# main.net
KiCad netlist of a schematic drawn in EAGLE
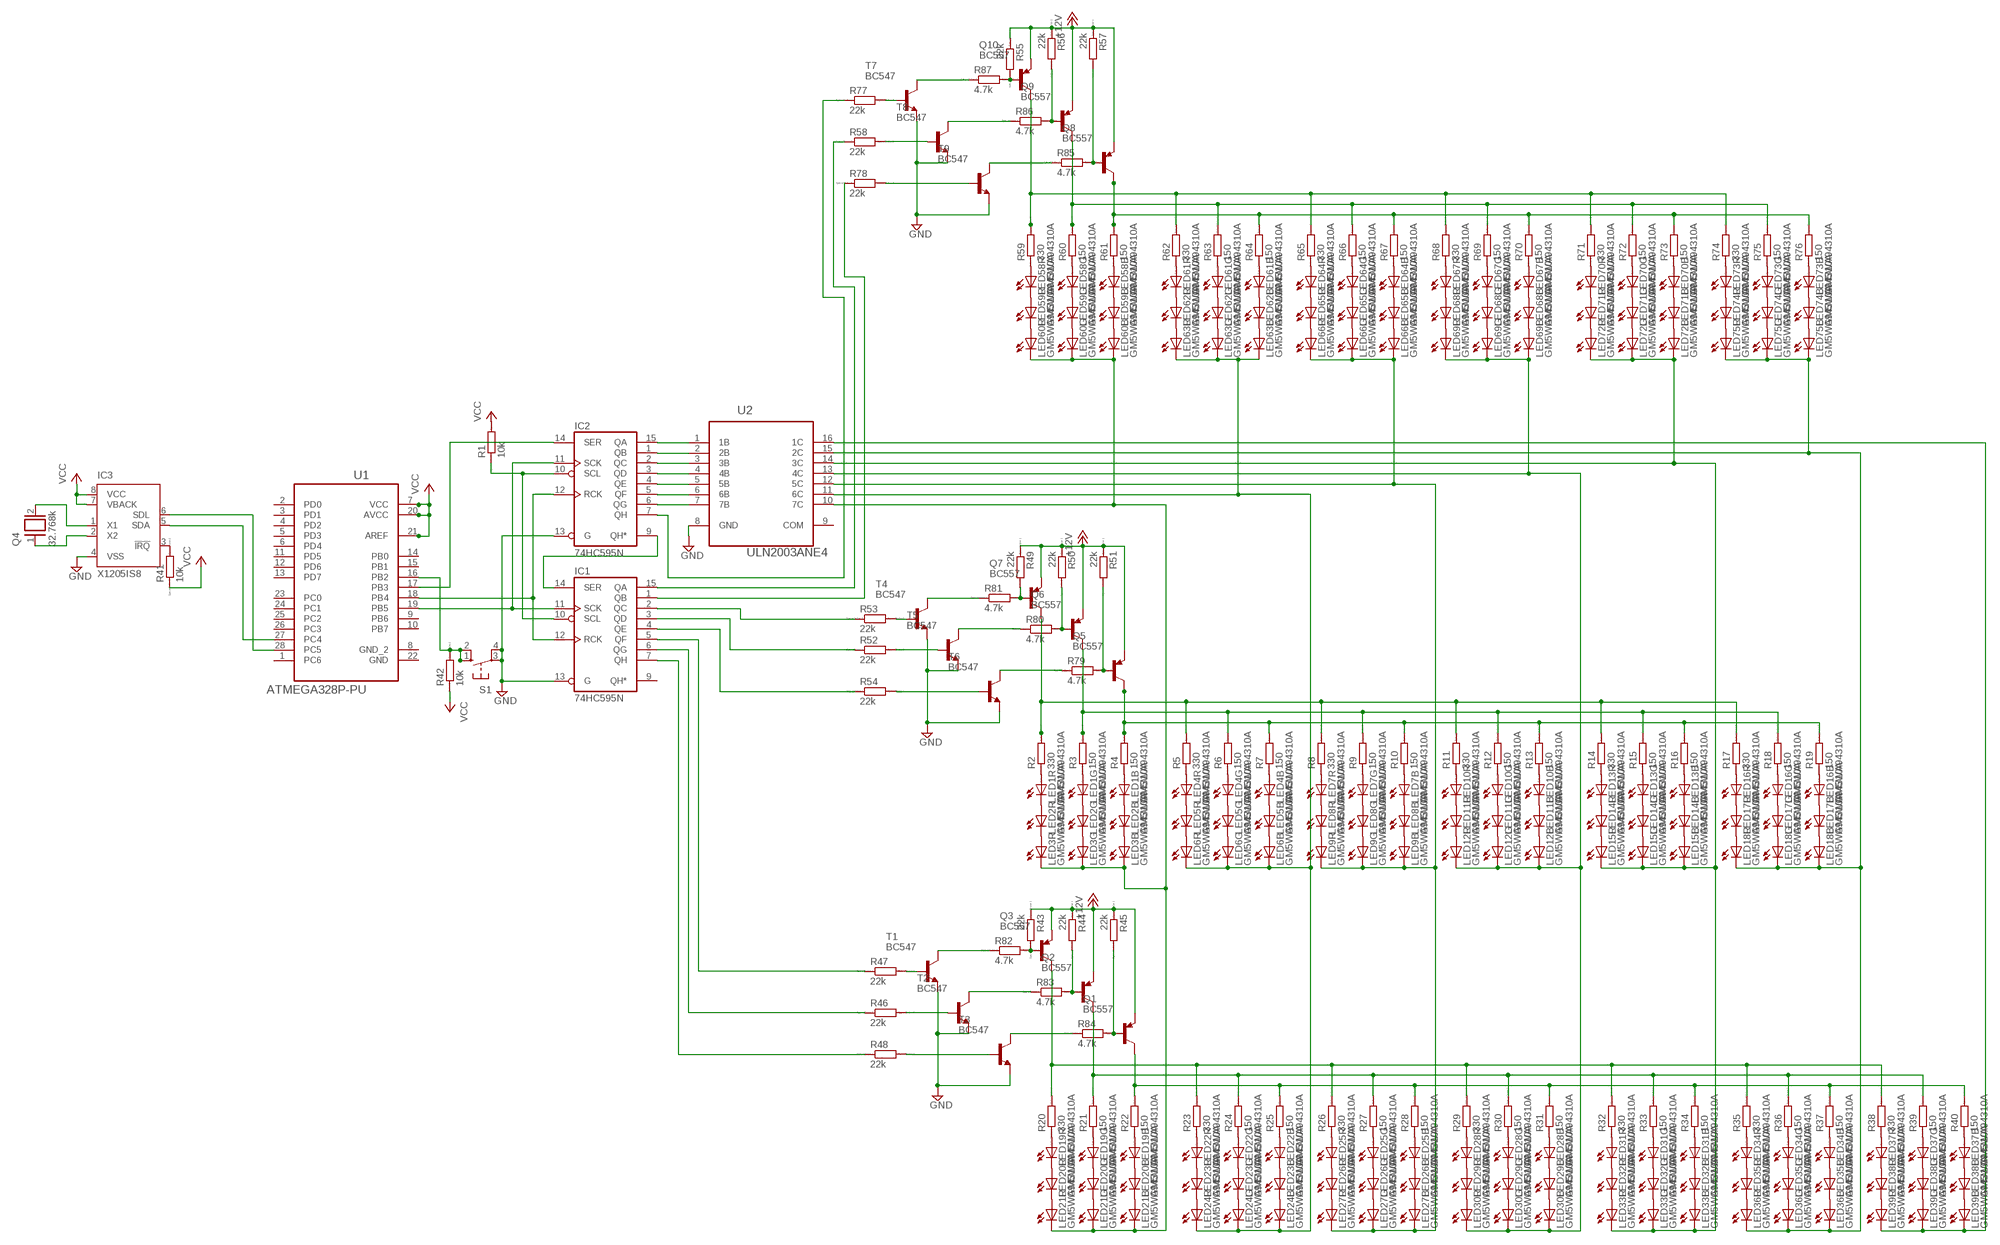
[diagram p0: schematic, sheet 1]

(export (version "E")
  (design (tool "Eeschema 10.0.6"))
  (components
    (comp (ref "IC1")
      (value "74HC595N")
      (footprint "eagle-import:DIL16")
      (libsource (lib "eagle-import") (part "74595NHC"))
    )
    (comp (ref "IC2")
      (value "74HC595N")
      (footprint "eagle-import:DIL16")
      (libsource (lib "eagle-import") (part "74595NHC"))
    )
    (comp (ref "IC3")
      (value "X1205IS8")
      (footprint "eagle-import:SO-08")
      (libsource (lib "eagle-import") (part "X1205S8I"))
    )
    (comp (ref "LED1")
      (value "GM5WA94310A")
      (footprint "eagle-import:GM5WA94310A")
      (libsource (lib "eagle-import") (part "GM5WA94310A"))
    )
    (comp (ref "LED2")
      (value "GM5WA94310A")
      (footprint "eagle-import:GM5WA94310A")
      (libsource (lib "eagle-import") (part "GM5WA94310A"))
    )
    (comp (ref "LED3")
      (value "GM5WA94310A")
      (footprint "eagle-import:GM5WA94310A")
      (libsource (lib "eagle-import") (part "GM5WA94310A"))
    )
    (comp (ref "LED4")
      (value "GM5WA94310A")
      (footprint "eagle-import:GM5WA94310A")
      (libsource (lib "eagle-import") (part "GM5WA94310A"))
    )
    (comp (ref "LED5")
      (value "GM5WA94310A")
      (footprint "eagle-import:GM5WA94310A")
      (libsource (lib "eagle-import") (part "GM5WA94310A"))
    )
    (comp (ref "LED6")
      (value "GM5WA94310A")
      (footprint "eagle-import:GM5WA94310A")
      (libsource (lib "eagle-import") (part "GM5WA94310A"))
    )
    (comp (ref "LED7")
      (value "GM5WA94310A")
      (footprint "eagle-import:GM5WA94310A")
      (libsource (lib "eagle-import") (part "GM5WA94310A"))
    )
    (comp (ref "LED8")
      (value "GM5WA94310A")
      (footprint "eagle-import:GM5WA94310A")
      (libsource (lib "eagle-import") (part "GM5WA94310A"))
    )
    (comp (ref "LED9")
      (value "GM5WA94310A")
      (footprint "eagle-import:GM5WA94310A")
      (libsource (lib "eagle-import") (part "GM5WA94310A"))
    )
    (comp (ref "LED10")
      (value "GM5WA94310A")
      (footprint "eagle-import:GM5WA94310A")
      (libsource (lib "eagle-import") (part "GM5WA94310A"))
    )
    (comp (ref "LED11")
      (value "GM5WA94310A")
      (footprint "eagle-import:GM5WA94310A")
      (libsource (lib "eagle-import") (part "GM5WA94310A"))
    )
    (comp (ref "LED12")
      (value "GM5WA94310A")
      (footprint "eagle-import:GM5WA94310A")
      (libsource (lib "eagle-import") (part "GM5WA94310A"))
    )
    (comp (ref "LED13")
      (value "GM5WA94310A")
      (footprint "eagle-import:GM5WA94310A")
      (libsource (lib "eagle-import") (part "GM5WA94310A"))
    )
    (comp (ref "LED14")
      (value "GM5WA94310A")
      (footprint "eagle-import:GM5WA94310A")
      (libsource (lib "eagle-import") (part "GM5WA94310A"))
    )
    (comp (ref "LED15")
      (value "GM5WA94310A")
      (footprint "eagle-import:GM5WA94310A")
      (libsource (lib "eagle-import") (part "GM5WA94310A"))
    )
    (comp (ref "LED16")
      (value "GM5WA94310A")
      (footprint "eagle-import:GM5WA94310A")
      (libsource (lib "eagle-import") (part "GM5WA94310A"))
    )
    (comp (ref "LED17")
      (value "GM5WA94310A")
      (footprint "eagle-import:GM5WA94310A")
      (libsource (lib "eagle-import") (part "GM5WA94310A"))
    )
    (comp (ref "LED18")
      (value "GM5WA94310A")
      (footprint "eagle-import:GM5WA94310A")
      (libsource (lib "eagle-import") (part "GM5WA94310A"))
    )
    (comp (ref "LED19")
      (value "GM5WA94310A")
      (footprint "eagle-import:GM5WA94310A")
      (libsource (lib "eagle-import") (part "GM5WA94310A"))
    )
    (comp (ref "LED20")
      (value "GM5WA94310A")
      (footprint "eagle-import:GM5WA94310A")
      (libsource (lib "eagle-import") (part "GM5WA94310A"))
    )
    (comp (ref "LED21")
      (value "GM5WA94310A")
      (footprint "eagle-import:GM5WA94310A")
      (libsource (lib "eagle-import") (part "GM5WA94310A"))
    )
    (comp (ref "LED22")
      (value "GM5WA94310A")
      (footprint "eagle-import:GM5WA94310A")
      (libsource (lib "eagle-import") (part "GM5WA94310A"))
    )
    (comp (ref "LED23")
      (value "GM5WA94310A")
      (footprint "eagle-import:GM5WA94310A")
      (libsource (lib "eagle-import") (part "GM5WA94310A"))
    )
    (comp (ref "LED24")
      (value "GM5WA94310A")
      (footprint "eagle-import:GM5WA94310A")
      (libsource (lib "eagle-import") (part "GM5WA94310A"))
    )
    (comp (ref "LED25")
      (value "GM5WA94310A")
      (footprint "eagle-import:GM5WA94310A")
      (libsource (lib "eagle-import") (part "GM5WA94310A"))
    )
    (comp (ref "LED26")
      (value "GM5WA94310A")
      (footprint "eagle-import:GM5WA94310A")
      (libsource (lib "eagle-import") (part "GM5WA94310A"))
    )
    (comp (ref "LED27")
      (value "GM5WA94310A")
      (footprint "eagle-import:GM5WA94310A")
      (libsource (lib "eagle-import") (part "GM5WA94310A"))
    )
    (comp (ref "LED28")
      (value "GM5WA94310A")
      (footprint "eagle-import:GM5WA94310A")
      (libsource (lib "eagle-import") (part "GM5WA94310A"))
    )
    (comp (ref "LED29")
      (value "GM5WA94310A")
      (footprint "eagle-import:GM5WA94310A")
      (libsource (lib "eagle-import") (part "GM5WA94310A"))
    )
    (comp (ref "LED30")
      (value "GM5WA94310A")
      (footprint "eagle-import:GM5WA94310A")
      (libsource (lib "eagle-import") (part "GM5WA94310A"))
    )
    (comp (ref "LED31")
      (value "GM5WA94310A")
      (footprint "eagle-import:GM5WA94310A")
      (libsource (lib "eagle-import") (part "GM5WA94310A"))
    )
    (comp (ref "LED32")
      (value "GM5WA94310A")
      (footprint "eagle-import:GM5WA94310A")
      (libsource (lib "eagle-import") (part "GM5WA94310A"))
    )
    (comp (ref "LED33")
      (value "GM5WA94310A")
      (footprint "eagle-import:GM5WA94310A")
      (libsource (lib "eagle-import") (part "GM5WA94310A"))
    )
    (comp (ref "LED34")
      (value "GM5WA94310A")
      (footprint "eagle-import:GM5WA94310A")
      (libsource (lib "eagle-import") (part "GM5WA94310A"))
    )
    (comp (ref "LED35")
      (value "GM5WA94310A")
      (footprint "eagle-import:GM5WA94310A")
      (libsource (lib "eagle-import") (part "GM5WA94310A"))
    )
    (comp (ref "LED36")
      (value "GM5WA94310A")
      (footprint "eagle-import:GM5WA94310A")
      (libsource (lib "eagle-import") (part "GM5WA94310A"))
    )
    (comp (ref "LED37")
      (value "GM5WA94310A")
      (footprint "eagle-import:GM5WA94310A")
      (libsource (lib "eagle-import") (part "GM5WA94310A"))
    )
    (comp (ref "LED38")
      (value "GM5WA94310A")
      (footprint "eagle-import:GM5WA94310A")
      (libsource (lib "eagle-import") (part "GM5WA94310A"))
    )
    (comp (ref "LED39")
      (value "GM5WA94310A")
      (footprint "eagle-import:GM5WA94310A")
      (libsource (lib "eagle-import") (part "GM5WA94310A"))
    )
    (comp (ref "LED58")
      (value "GM5WA94310A")
      (footprint "eagle-import:GM5WA94310A")
      (libsource (lib "eagle-import") (part "GM5WA94310A"))
    )
    (comp (ref "LED59")
      (value "GM5WA94310A")
      (footprint "eagle-import:GM5WA94310A")
      (libsource (lib "eagle-import") (part "GM5WA94310A"))
    )
    (comp (ref "LED60")
      (value "GM5WA94310A")
      (footprint "eagle-import:GM5WA94310A")
      (libsource (lib "eagle-import") (part "GM5WA94310A"))
    )
    (comp (ref "LED61")
      (value "GM5WA94310A")
      (footprint "eagle-import:GM5WA94310A")
      (libsource (lib "eagle-import") (part "GM5WA94310A"))
    )
    (comp (ref "LED62")
      (value "GM5WA94310A")
      (footprint "eagle-import:GM5WA94310A")
      (libsource (lib "eagle-import") (part "GM5WA94310A"))
    )
    (comp (ref "LED63")
      (value "GM5WA94310A")
      (footprint "eagle-import:GM5WA94310A")
      (libsource (lib "eagle-import") (part "GM5WA94310A"))
    )
    (comp (ref "LED64")
      (value "GM5WA94310A")
      (footprint "eagle-import:GM5WA94310A")
      (libsource (lib "eagle-import") (part "GM5WA94310A"))
    )
    (comp (ref "LED65")
      (value "GM5WA94310A")
      (footprint "eagle-import:GM5WA94310A")
      (libsource (lib "eagle-import") (part "GM5WA94310A"))
    )
    (comp (ref "LED66")
      (value "GM5WA94310A")
      (footprint "eagle-import:GM5WA94310A")
      (libsource (lib "eagle-import") (part "GM5WA94310A"))
    )
    (comp (ref "LED67")
      (value "GM5WA94310A")
      (footprint "eagle-import:GM5WA94310A")
      (libsource (lib "eagle-import") (part "GM5WA94310A"))
    )
    (comp (ref "LED68")
      (value "GM5WA94310A")
      (footprint "eagle-import:GM5WA94310A")
      (libsource (lib "eagle-import") (part "GM5WA94310A"))
    )
    (comp (ref "LED69")
      (value "GM5WA94310A")
      (footprint "eagle-import:GM5WA94310A")
      (libsource (lib "eagle-import") (part "GM5WA94310A"))
    )
    (comp (ref "LED70")
      (value "GM5WA94310A")
      (footprint "eagle-import:GM5WA94310A")
      (libsource (lib "eagle-import") (part "GM5WA94310A"))
    )
    (comp (ref "LED71")
      (value "GM5WA94310A")
      (footprint "eagle-import:GM5WA94310A")
      (libsource (lib "eagle-import") (part "GM5WA94310A"))
    )
    (comp (ref "LED72")
      (value "GM5WA94310A")
      (footprint "eagle-import:GM5WA94310A")
      (libsource (lib "eagle-import") (part "GM5WA94310A"))
    )
    (comp (ref "LED73")
      (value "GM5WA94310A")
      (footprint "eagle-import:GM5WA94310A")
      (libsource (lib "eagle-import") (part "GM5WA94310A"))
    )
    (comp (ref "LED74")
      (value "GM5WA94310A")
      (footprint "eagle-import:GM5WA94310A")
      (libsource (lib "eagle-import") (part "GM5WA94310A"))
    )
    (comp (ref "LED75")
      (value "GM5WA94310A")
      (footprint "eagle-import:GM5WA94310A")
      (libsource (lib "eagle-import") (part "GM5WA94310A"))
    )
    (comp (ref "Q1")
      (value "BC557")
      (footprint "eagle-import:TO92-EBC")
      (libsource (lib "eagle-import") (part "BC557"))
    )
    (comp (ref "Q2")
      (value "BC557")
      (footprint "eagle-import:TO92-EBC")
      (libsource (lib "eagle-import") (part "BC557"))
    )
    (comp (ref "Q3")
      (value "BC557")
      (footprint "eagle-import:TO92-EBC")
      (libsource (lib "eagle-import") (part "BC557"))
    )
    (comp (ref "Q4")
      (value "32.768k")
      (footprint "eagle-import:QS")
      (libsource (lib "eagle-import") (part "XTAL/S"))
    )
    (comp (ref "Q5")
      (value "BC557")
      (footprint "eagle-import:TO92-EBC")
      (libsource (lib "eagle-import") (part "BC557"))
    )
    (comp (ref "Q6")
      (value "BC557")
      (footprint "eagle-import:TO92-EBC")
      (libsource (lib "eagle-import") (part "BC557"))
    )
    (comp (ref "Q7")
      (value "BC557")
      (footprint "eagle-import:TO92-EBC")
      (libsource (lib "eagle-import") (part "BC557"))
    )
    (comp (ref "Q8")
      (value "BC557")
      (footprint "eagle-import:TO92-EBC")
      (libsource (lib "eagle-import") (part "BC557"))
    )
    (comp (ref "Q9")
      (value "BC557")
      (footprint "eagle-import:TO92-EBC")
      (libsource (lib "eagle-import") (part "BC557"))
    )
    (comp (ref "Q10")
      (value "BC557")
      (footprint "eagle-import:TO92-EBC")
      (libsource (lib "eagle-import") (part "BC557"))
    )
    (comp (ref "R1")
      (value "10k")
      (footprint "eagle-import:0204_7")
      (libsource (lib "eagle-import") (part "R0204/7"))
    )
    (comp (ref "R2")
      (value "330")
      (footprint "eagle-import:0204_7")
      (libsource (lib "eagle-import") (part "R0204/7"))
    )
    (comp (ref "R3")
      (value "150")
      (footprint "eagle-import:0204_7")
      (libsource (lib "eagle-import") (part "R0204/7"))
    )
    (comp (ref "R4")
      (value "150")
      (footprint "eagle-import:0204_7")
      (libsource (lib "eagle-import") (part "R0204/7"))
    )
    (comp (ref "R5")
      (value "330")
      (footprint "eagle-import:0204_7")
      (libsource (lib "eagle-import") (part "R0204/7"))
    )
    (comp (ref "R6")
      (value "150")
      (footprint "eagle-import:0204_7")
      (libsource (lib "eagle-import") (part "R0204/7"))
    )
    (comp (ref "R7")
      (value "150")
      (footprint "eagle-import:0204_7")
      (libsource (lib "eagle-import") (part "R0204/7"))
    )
    (comp (ref "R8")
      (value "330")
      (footprint "eagle-import:0204_7")
      (libsource (lib "eagle-import") (part "R0204/7"))
    )
    (comp (ref "R9")
      (value "150")
      (footprint "eagle-import:0204_7")
      (libsource (lib "eagle-import") (part "R0204/7"))
    )
    (comp (ref "R10")
      (value "150")
      (footprint "eagle-import:0204_7")
      (libsource (lib "eagle-import") (part "R0204/7"))
    )
    (comp (ref "R11")
      (value "330")
      (footprint "eagle-import:0204_7")
      (libsource (lib "eagle-import") (part "R0204/7"))
    )
    (comp (ref "R12")
      (value "150")
      (footprint "eagle-import:0204_7")
      (libsource (lib "eagle-import") (part "R0204/7"))
    )
    (comp (ref "R13")
      (value "150")
      (footprint "eagle-import:0204_7")
      (libsource (lib "eagle-import") (part "R0204/7"))
    )
    (comp (ref "R14")
      (value "330")
      (footprint "eagle-import:0204_7")
      (libsource (lib "eagle-import") (part "R0204/7"))
    )
    (comp (ref "R15")
      (value "150")
      (footprint "eagle-import:0204_7")
      (libsource (lib "eagle-import") (part "R0204/7"))
    )
    (comp (ref "R16")
      (value "150")
      (footprint "eagle-import:0204_7")
      (libsource (lib "eagle-import") (part "R0204/7"))
    )
    (comp (ref "R17")
      (value "330")
      (footprint "eagle-import:0204_7")
      (libsource (lib "eagle-import") (part "R0204/7"))
    )
    (comp (ref "R18")
      (value "150")
      (footprint "eagle-import:0204_7")
      (libsource (lib "eagle-import") (part "R0204/7"))
    )
    (comp (ref "R19")
      (value "150")
      (footprint "eagle-import:0204_7")
      (libsource (lib "eagle-import") (part "R0204/7"))
    )
    (comp (ref "R20")
      (value "330")
      (footprint "eagle-import:0204_7")
      (libsource (lib "eagle-import") (part "R0204/7"))
    )
    (comp (ref "R21")
      (value "150")
      (footprint "eagle-import:0204_7")
      (libsource (lib "eagle-import") (part "R0204/7"))
    )
    (comp (ref "R22")
      (value "150")
      (footprint "eagle-import:0204_7")
      (libsource (lib "eagle-import") (part "R0204/7"))
    )
    (comp (ref "R23")
      (value "330")
      (footprint "eagle-import:0204_7")
      (libsource (lib "eagle-import") (part "R0204/7"))
    )
    (comp (ref "R24")
      (value "150")
      (footprint "eagle-import:0204_7")
      (libsource (lib "eagle-import") (part "R0204/7"))
    )
    (comp (ref "R25")
      (value "150")
      (footprint "eagle-import:0204_7")
      (libsource (lib "eagle-import") (part "R0204/7"))
    )
    (comp (ref "R26")
      (value "330")
      (footprint "eagle-import:0204_7")
      (libsource (lib "eagle-import") (part "R0204/7"))
    )
    (comp (ref "R27")
      (value "150")
      (footprint "eagle-import:0204_7")
      (libsource (lib "eagle-import") (part "R0204/7"))
    )
    (comp (ref "R28")
      (value "150")
      (footprint "eagle-import:0204_7")
      (libsource (lib "eagle-import") (part "R0204/7"))
    )
    (comp (ref "R29")
      (value "330")
      (footprint "eagle-import:0204_7")
      (libsource (lib "eagle-import") (part "R0204/7"))
    )
    (comp (ref "R30")
      (value "150")
      (footprint "eagle-import:0204_7")
      (libsource (lib "eagle-import") (part "R0204/7"))
    )
    (comp (ref "R31")
      (value "150")
      (footprint "eagle-import:0204_7")
      (libsource (lib "eagle-import") (part "R0204/7"))
    )
    (comp (ref "R32")
      (value "330")
      (footprint "eagle-import:0204_7")
      (libsource (lib "eagle-import") (part "R0204/7"))
    )
    (comp (ref "R33")
      (value "150")
      (footprint "eagle-import:0204_7")
      (libsource (lib "eagle-import") (part "R0204/7"))
    )
    (comp (ref "R34")
      (value "150")
      (footprint "eagle-import:0204_7")
      (libsource (lib "eagle-import") (part "R0204/7"))
    )
    (comp (ref "R35")
      (value "330")
      (footprint "eagle-import:0204_7")
      (libsource (lib "eagle-import") (part "R0204/7"))
    )
    (comp (ref "R36")
      (value "150")
      (footprint "eagle-import:0204_7")
      (libsource (lib "eagle-import") (part "R0204/7"))
    )
    (comp (ref "R37")
      (value "150")
      (footprint "eagle-import:0204_7")
      (libsource (lib "eagle-import") (part "R0204/7"))
    )
    (comp (ref "R38")
      (value "330")
      (footprint "eagle-import:0204_7")
      (libsource (lib "eagle-import") (part "R0204/7"))
    )
    (comp (ref "R39")
      (value "150")
      (footprint "eagle-import:0204_7")
      (libsource (lib "eagle-import") (part "R0204/7"))
    )
    (comp (ref "R40")
      (value "150")
      (footprint "eagle-import:0204_7")
      (libsource (lib "eagle-import") (part "R0204/7"))
    )
    (comp (ref "R41")
      (value "10k")
      (footprint "eagle-import:0204_7")
      (libsource (lib "eagle-import") (part "R0204/7"))
    )
    (comp (ref "R42")
      (value "10k")
      (footprint "eagle-import:0204_7")
      (libsource (lib "eagle-import") (part "R0204/7"))
    )
    (comp (ref "R43")
      (value "22k")
      (footprint "eagle-import:0204_7")
      (libsource (lib "eagle-import") (part "R0204/7"))
    )
    (comp (ref "R44")
      (value "22k")
      (footprint "eagle-import:0204_7")
      (libsource (lib "eagle-import") (part "R0204/7"))
    )
    (comp (ref "R45")
      (value "22k")
      (footprint "eagle-import:0204_7")
      (libsource (lib "eagle-import") (part "R0204/7"))
    )
    (comp (ref "R46")
      (value "22k")
      (footprint "eagle-import:0204_7")
      (libsource (lib "eagle-import") (part "R0204/7"))
    )
    (comp (ref "R47")
      (value "22k")
      (footprint "eagle-import:0204_7")
      (libsource (lib "eagle-import") (part "R0204/7"))
    )
    (comp (ref "R48")
      (value "22k")
      (footprint "eagle-import:0204_7")
      (libsource (lib "eagle-import") (part "R0204/7"))
    )
    (comp (ref "R49")
      (value "22k")
      (footprint "eagle-import:0204_7")
      (libsource (lib "eagle-import") (part "R0204/7"))
    )
    (comp (ref "R50")
      (value "22k")
      (footprint "eagle-import:0204_7")
      (libsource (lib "eagle-import") (part "R0204/7"))
    )
    (comp (ref "R51")
      (value "22k")
      (footprint "eagle-import:0204_7")
      (libsource (lib "eagle-import") (part "R0204/7"))
    )
    (comp (ref "R52")
      (value "22k")
      (footprint "eagle-import:0204_7")
      (libsource (lib "eagle-import") (part "R0204/7"))
    )
    (comp (ref "R53")
      (value "22k")
      (footprint "eagle-import:0204_7")
      (libsource (lib "eagle-import") (part "R0204/7"))
    )
    (comp (ref "R54")
      (value "22k")
      (footprint "eagle-import:0204_7")
      (libsource (lib "eagle-import") (part "R0204/7"))
    )
    (comp (ref "R55")
      (value "22k")
      (footprint "eagle-import:0204_7")
      (libsource (lib "eagle-import") (part "R0204/7"))
    )
    (comp (ref "R56")
      (value "22k")
      (footprint "eagle-import:0204_7")
      (libsource (lib "eagle-import") (part "R0204/7"))
    )
    (comp (ref "R57")
      (value "22k")
      (footprint "eagle-import:0204_7")
      (libsource (lib "eagle-import") (part "R0204/7"))
    )
    (comp (ref "R58")
      (value "22k")
      (footprint "eagle-import:0204_7")
      (libsource (lib "eagle-import") (part "R0204/7"))
    )
    (comp (ref "R59")
      (value "330")
      (footprint "eagle-import:0204_7")
      (libsource (lib "eagle-import") (part "R0204/7"))
    )
    (comp (ref "R60")
      (value "150")
      (footprint "eagle-import:0204_7")
      (libsource (lib "eagle-import") (part "R0204/7"))
    )
    (comp (ref "R61")
      (value "150")
      (footprint "eagle-import:0204_7")
      (libsource (lib "eagle-import") (part "R0204/7"))
    )
    (comp (ref "R62")
      (value "330")
      (footprint "eagle-import:0204_7")
      (libsource (lib "eagle-import") (part "R0204/7"))
    )
    (comp (ref "R63")
      (value "150")
      (footprint "eagle-import:0204_7")
      (libsource (lib "eagle-import") (part "R0204/7"))
    )
    (comp (ref "R64")
      (value "150")
      (footprint "eagle-import:0204_7")
      (libsource (lib "eagle-import") (part "R0204/7"))
    )
    (comp (ref "R65")
      (value "330")
      (footprint "eagle-import:0204_7")
      (libsource (lib "eagle-import") (part "R0204/7"))
    )
    (comp (ref "R66")
      (value "150")
      (footprint "eagle-import:0204_7")
      (libsource (lib "eagle-import") (part "R0204/7"))
    )
    (comp (ref "R67")
      (value "150")
      (footprint "eagle-import:0204_7")
      (libsource (lib "eagle-import") (part "R0204/7"))
    )
    (comp (ref "R68")
      (value "330")
      (footprint "eagle-import:0204_7")
      (libsource (lib "eagle-import") (part "R0204/7"))
    )
    (comp (ref "R69")
      (value "150")
      (footprint "eagle-import:0204_7")
      (libsource (lib "eagle-import") (part "R0204/7"))
    )
    (comp (ref "R70")
      (value "150")
      (footprint "eagle-import:0204_7")
      (libsource (lib "eagle-import") (part "R0204/7"))
    )
    (comp (ref "R71")
      (value "330")
      (footprint "eagle-import:0204_7")
      (libsource (lib "eagle-import") (part "R0204/7"))
    )
    (comp (ref "R72")
      (value "150")
      (footprint "eagle-import:0204_7")
      (libsource (lib "eagle-import") (part "R0204/7"))
    )
    (comp (ref "R73")
      (value "150")
      (footprint "eagle-import:0204_7")
      (libsource (lib "eagle-import") (part "R0204/7"))
    )
    (comp (ref "R74")
      (value "330")
      (footprint "eagle-import:0204_7")
      (libsource (lib "eagle-import") (part "R0204/7"))
    )
    (comp (ref "R75")
      (value "150")
      (footprint "eagle-import:0204_7")
      (libsource (lib "eagle-import") (part "R0204/7"))
    )
    (comp (ref "R76")
      (value "150")
      (footprint "eagle-import:0204_7")
      (libsource (lib "eagle-import") (part "R0204/7"))
    )
    (comp (ref "R77")
      (value "22k")
      (footprint "eagle-import:0204_7")
      (libsource (lib "eagle-import") (part "R0204/7"))
    )
    (comp (ref "R78")
      (value "22k")
      (footprint "eagle-import:0204_7")
      (libsource (lib "eagle-import") (part "R0204/7"))
    )
    (comp (ref "R79")
      (value "4.7k")
      (footprint "eagle-import:0204_7")
      (libsource (lib "eagle-import") (part "R0204/7"))
    )
    (comp (ref "R80")
      (value "4.7k")
      (footprint "eagle-import:0204_7")
      (libsource (lib "eagle-import") (part "R0204/7"))
    )
    (comp (ref "R81")
      (value "4.7k")
      (footprint "eagle-import:0204_7")
      (libsource (lib "eagle-import") (part "R0204/7"))
    )
    (comp (ref "R82")
      (value "4.7k")
      (footprint "eagle-import:0204_7")
      (libsource (lib "eagle-import") (part "R0204/7"))
    )
    (comp (ref "R83")
      (value "4.7k")
      (footprint "eagle-import:0204_7")
      (libsource (lib "eagle-import") (part "R0204/7"))
    )
    (comp (ref "R84")
      (value "4.7k")
      (footprint "eagle-import:0204_7")
      (libsource (lib "eagle-import") (part "R0204/7"))
    )
    (comp (ref "R85")
      (value "4.7k")
      (footprint "eagle-import:0204_7")
      (libsource (lib "eagle-import") (part "R0204/7"))
    )
    (comp (ref "R86")
      (value "4.7k")
      (footprint "eagle-import:0204_7")
      (libsource (lib "eagle-import") (part "R0204/7"))
    )
    (comp (ref "R87")
      (value "4.7k")
      (footprint "eagle-import:0204_7")
      (libsource (lib "eagle-import") (part "R0204/7"))
    )
    (comp (ref "S1")
      (value "10-XX")
      (footprint "eagle-import:B3F-10XX")
      (fields (field (name "MPN") "B3F-1000"))
      (libsource (lib "eagle-import") (part "10-XX"))
    )
    (comp (ref "T1")
      (value "BC547")
      (footprint "eagle-import:TO92")
      (libsource (lib "eagle-import") (part "BC547"))
    )
    (comp (ref "T2")
      (value "BC547")
      (footprint "eagle-import:TO92")
      (libsource (lib "eagle-import") (part "BC547"))
    )
    (comp (ref "T3")
      (value "BC547")
      (footprint "eagle-import:TO92")
      (libsource (lib "eagle-import") (part "BC547"))
    )
    (comp (ref "T4")
      (value "BC547")
      (footprint "eagle-import:TO92")
      (libsource (lib "eagle-import") (part "BC547"))
    )
    (comp (ref "T5")
      (value "BC547")
      (footprint "eagle-import:TO92")
      (libsource (lib "eagle-import") (part "BC547"))
    )
    (comp (ref "T6")
      (value "BC547")
      (footprint "eagle-import:TO92")
      (libsource (lib "eagle-import") (part "BC547"))
    )
    (comp (ref "T7")
      (value "BC547")
      (footprint "eagle-import:TO92")
      (libsource (lib "eagle-import") (part "BC547"))
    )
    (comp (ref "T8")
      (value "BC547")
      (footprint "eagle-import:TO92")
      (libsource (lib "eagle-import") (part "BC547"))
    )
    (comp (ref "T9")
      (value "BC547")
      (footprint "eagle-import:TO92")
      (libsource (lib "eagle-import") (part "BC547"))
    )
    (comp (ref "U1")
      (value "ATMEGA328P-PU")
      (footprint "eagle-import:DIP254P762X457-28")
      (libsource (lib "eagle-import") (part "ATMEGA328P-PU"))
    )
    (comp (ref "U2")
      (value "ULN2003ANE4")
      (footprint "eagle-import:DIP254P762X508-16")
      (libsource (lib "eagle-import") (part "ULN2003ANE4"))
    )
  )
  (nets
    (net (code "1") (name "+12V") (class "Default")
      (node (ref "Q1") (pin "E") (pinfunction "E_E") (pintype "passive"))
      (node (ref "Q10") (pin "E") (pinfunction "E_E") (pintype "passive"))
      (node (ref "Q2") (pin "E") (pinfunction "E_E") (pintype "passive"))
      (node (ref "Q3") (pin "E") (pinfunction "E_E") (pintype "passive"))
      (node (ref "Q5") (pin "E") (pinfunction "E_E") (pintype "passive"))
      (node (ref "Q6") (pin "E") (pinfunction "E_E") (pintype "passive"))
      (node (ref "Q7") (pin "E") (pinfunction "E_E") (pintype "passive"))
      (node (ref "Q8") (pin "E") (pinfunction "E_E") (pintype "passive"))
      (node (ref "Q9") (pin "E") (pinfunction "E_E") (pintype "passive"))
      (node (ref "R43") (pin "1") (pinfunction "1_1") (pintype "passive"))
      (node (ref "R44") (pin "1") (pinfunction "1_1") (pintype "passive"))
      (node (ref "R45") (pin "1") (pinfunction "1_1") (pintype "passive"))
      (node (ref "R49") (pin "1") (pinfunction "1_1") (pintype "passive"))
      (node (ref "R50") (pin "1") (pinfunction "1_1") (pintype "passive"))
      (node (ref "R51") (pin "1") (pinfunction "1_1") (pintype "passive"))
      (node (ref "R55") (pin "1") (pinfunction "1_1") (pintype "passive"))
      (node (ref "R56") (pin "1") (pinfunction "1_1") (pintype "passive"))
      (node (ref "R57") (pin "1") (pinfunction "1_1") (pintype "passive"))
    )
    (net (code "2") (name "GND") (class "Default")
      (node (ref "IC1") (pin "13") (pinfunction "G_13") (pintype "input"))
      (node (ref "IC2") (pin "13") (pinfunction "G_13") (pintype "input"))
      (node (ref "IC3") (pin "4") (pinfunction "VSS_4") (pintype "power_in"))
      (node (ref "S1") (pin "3") (pinfunction "P_3") (pintype "passive"))
      (node (ref "S1") (pin "4") (pinfunction "P1_4") (pintype "passive"))
      (node (ref "T1") (pin "1") (pinfunction "E_1") (pintype "passive"))
      (node (ref "T2") (pin "1") (pinfunction "E_1") (pintype "passive"))
      (node (ref "T3") (pin "1") (pinfunction "E_1") (pintype "passive"))
      (node (ref "T4") (pin "1") (pinfunction "E_1") (pintype "passive"))
      (node (ref "T5") (pin "1") (pinfunction "E_1") (pintype "passive"))
      (node (ref "T6") (pin "1") (pinfunction "E_1") (pintype "passive"))
      (node (ref "T7") (pin "1") (pinfunction "E_1") (pintype "passive"))
      (node (ref "T8") (pin "1") (pinfunction "E_1") (pintype "passive"))
      (node (ref "T9") (pin "1") (pinfunction "E_1") (pintype "passive"))
      (node (ref "U2") (pin "8") (pinfunction "GND_8") (pintype "passive"))
    )
    (net (code "3") (name "Net-(IC1A-QA)") (class "Default")
      (node (ref "IC1") (pin "15") (pinfunction "QA_15") (pintype "tri_state"))
      (node (ref "R58") (pin "1") (pinfunction "1_1") (pintype "passive"))
    )
    (net (code "4") (name "Net-(IC1A-QB)") (class "Default")
      (node (ref "IC1") (pin "1") (pinfunction "QB_1") (pintype "tri_state"))
      (node (ref "R78") (pin "1") (pinfunction "1_1") (pintype "passive"))
    )
    (net (code "5") (name "Net-(IC1A-QC)") (class "Default")
      (node (ref "IC1") (pin "2") (pinfunction "QC_2") (pintype "tri_state"))
      (node (ref "R53") (pin "1") (pinfunction "1_1") (pintype "passive"))
    )
    (net (code "6") (name "Net-(IC1A-QD)") (class "Default")
      (node (ref "IC1") (pin "3") (pinfunction "QD_3") (pintype "tri_state"))
      (node (ref "R52") (pin "1") (pinfunction "1_1") (pintype "passive"))
    )
    (net (code "7") (name "Net-(IC1A-QE)") (class "Default")
      (node (ref "IC1") (pin "4") (pinfunction "QE_4") (pintype "tri_state"))
      (node (ref "R54") (pin "1") (pinfunction "1_1") (pintype "passive"))
    )
    (net (code "8") (name "Net-(IC1A-QF)") (class "Default")
      (node (ref "IC1") (pin "5") (pinfunction "QF_5") (pintype "tri_state"))
      (node (ref "R47") (pin "1") (pinfunction "1_1") (pintype "passive"))
    )
    (net (code "9") (name "Net-(IC1A-QG)") (class "Default")
      (node (ref "IC1") (pin "6") (pinfunction "QG_6") (pintype "tri_state"))
      (node (ref "R46") (pin "1") (pinfunction "1_1") (pintype "passive"))
    )
    (net (code "10") (name "Net-(IC1A-QH)") (class "Default")
      (node (ref "IC1") (pin "7") (pinfunction "QH_7") (pintype "tri_state"))
      (node (ref "R48") (pin "1") (pinfunction "1_1") (pintype "passive"))
    )
    (net (code "11") (name "Net-(IC1A-RCK)") (class "Default")
      (node (ref "IC1") (pin "12") (pinfunction "RCK_12") (pintype "input"))
      (node (ref "IC2") (pin "12") (pinfunction "RCK_12") (pintype "input"))
      (node (ref "U1") (pin "18") (pinfunction "PB4_18") (pintype "bidirectional"))
    )
    (net (code "12") (name "Net-(IC1A-SCK)") (class "Default")
      (node (ref "IC1") (pin "11") (pinfunction "SCK_11") (pintype "input"))
      (node (ref "IC2") (pin "11") (pinfunction "SCK_11") (pintype "input"))
      (node (ref "U1") (pin "19") (pinfunction "PB5_19") (pintype "bidirectional"))
    )
    (net (code "13") (name "Net-(IC1A-SCL)") (class "Default")
      (node (ref "IC1") (pin "10") (pinfunction "SCL_10") (pintype "input"))
      (node (ref "IC2") (pin "10") (pinfunction "SCL_10") (pintype "input"))
      (node (ref "R1") (pin "1") (pinfunction "1_1") (pintype "passive"))
    )
    (net (code "14") (name "Net-(IC1A-SER)") (class "Default")
      (node (ref "IC1") (pin "14") (pinfunction "SER_14") (pintype "input"))
      (node (ref "IC2") (pin "9") (pinfunction "QH*_9") (pintype "tri_state"))
    )
    (net (code "15") (name "Net-(IC2A-QA)") (class "Default")
      (node (ref "IC2") (pin "15") (pinfunction "QA_15") (pintype "tri_state"))
      (node (ref "U2") (pin "1") (pinfunction "1B_1") (pintype "input"))
    )
    (net (code "16") (name "Net-(IC2A-QB)") (class "Default")
      (node (ref "IC2") (pin "1") (pinfunction "QB_1") (pintype "tri_state"))
      (node (ref "U2") (pin "2") (pinfunction "2B_2") (pintype "input"))
    )
    (net (code "17") (name "Net-(IC2A-QC)") (class "Default")
      (node (ref "IC2") (pin "2") (pinfunction "QC_2") (pintype "tri_state"))
      (node (ref "U2") (pin "3") (pinfunction "3B_3") (pintype "input"))
    )
    (net (code "18") (name "Net-(IC2A-QD)") (class "Default")
      (node (ref "IC2") (pin "3") (pinfunction "QD_3") (pintype "tri_state"))
      (node (ref "U2") (pin "4") (pinfunction "4B_4") (pintype "input"))
    )
    (net (code "19") (name "Net-(IC2A-QE)") (class "Default")
      (node (ref "IC2") (pin "4") (pinfunction "QE_4") (pintype "tri_state"))
      (node (ref "U2") (pin "5") (pinfunction "5B_5") (pintype "input"))
    )
    (net (code "20") (name "Net-(IC2A-QF)") (class "Default")
      (node (ref "IC2") (pin "5") (pinfunction "QF_5") (pintype "tri_state"))
      (node (ref "U2") (pin "6") (pinfunction "6B_6") (pintype "input"))
    )
    (net (code "21") (name "Net-(IC2A-QG)") (class "Default")
      (node (ref "IC2") (pin "6") (pinfunction "QG_6") (pintype "tri_state"))
      (node (ref "U2") (pin "7") (pinfunction "7B_7") (pintype "input"))
    )
    (net (code "22") (name "Net-(IC2A-QH)") (class "Default")
      (node (ref "IC2") (pin "7") (pinfunction "QH_7") (pintype "tri_state"))
      (node (ref "R77") (pin "1") (pinfunction "1_1") (pintype "passive"))
    )
    (net (code "23") (name "Net-(IC2A-SER)") (class "Default")
      (node (ref "IC2") (pin "14") (pinfunction "SER_14") (pintype "input"))
      (node (ref "U1") (pin "17") (pinfunction "PB3_17") (pintype "bidirectional"))
    )
    (net (code "24") (name "Net-(IC3-SDA)") (class "Default")
      (node (ref "IC3") (pin "5") (pinfunction "SDA_5") (pintype "bidirectional"))
      (node (ref "U1") (pin "27") (pinfunction "PC4_27") (pintype "bidirectional"))
    )
    (net (code "25") (name "Net-(IC3-SDL)") (class "Default")
      (node (ref "IC3") (pin "6") (pinfunction "SDL_6") (pintype "input"))
      (node (ref "U1") (pin "28") (pinfunction "PC5_28") (pintype "bidirectional"))
    )
    (net (code "26") (name "Net-(IC3-X1)") (class "Default")
      (node (ref "IC3") (pin "1") (pinfunction "X1_1") (pintype "input"))
      (node (ref "Q4") (pin "2") (pinfunction "2_2") (pintype "passive"))
    )
    (net (code "27") (name "Net-(IC3-X2)") (class "Default")
      (node (ref "IC3") (pin "2") (pinfunction "X2_2") (pintype "output"))
      (node (ref "Q4") (pin "1") (pinfunction "1_1") (pintype "passive"))
    )
    (net (code "28") (name "Net-(IC3-~{IRQ})") (class "Default")
      (node (ref "IC3") (pin "3") (pinfunction "~{IRQ}_3") (pintype "output"))
      (node (ref "R41") (pin "2") (pinfunction "2_2") (pintype "passive"))
    )
    (net (code "29") (name "Net-(LED1A-A)") (class "Default")
      (node (ref "LED1") (pin "1") (pinfunction "A_1") (pintype "passive"))
      (node (ref "R4") (pin "1") (pinfunction "1_1") (pintype "passive"))
    )
    (net (code "30") (name "Net-(LED1A-C)") (class "Default")
      (node (ref "LED1") (pin "6") (pinfunction "C_6") (pintype "passive"))
      (node (ref "LED2") (pin "1") (pinfunction "A_1") (pintype "passive"))
    )
    (net (code "31") (name "Net-(LED1B-A)") (class "Default")
      (node (ref "LED1") (pin "3") (pinfunction "A_3") (pintype "passive"))
      (node (ref "R3") (pin "1") (pinfunction "1_1") (pintype "passive"))
    )
    (net (code "32") (name "Net-(LED1B-C)") (class "Default")
      (node (ref "LED1") (pin "4") (pinfunction "C_4") (pintype "passive"))
      (node (ref "LED2") (pin "3") (pinfunction "A_3") (pintype "passive"))
    )
    (net (code "33") (name "Net-(LED1C-A)") (class "Default")
      (node (ref "LED1") (pin "2") (pinfunction "A_2") (pintype "passive"))
      (node (ref "R2") (pin "1") (pinfunction "1_1") (pintype "passive"))
    )
    (net (code "34") (name "Net-(LED1C-C)") (class "Default")
      (node (ref "LED1") (pin "5") (pinfunction "C_5") (pintype "passive"))
      (node (ref "LED2") (pin "2") (pinfunction "A_2") (pintype "passive"))
    )
    (net (code "35") (name "Net-(LED2A-C)") (class "Default")
      (node (ref "LED2") (pin "6") (pinfunction "C_6") (pintype "passive"))
      (node (ref "LED3") (pin "1") (pinfunction "A_1") (pintype "passive"))
    )
    (net (code "36") (name "Net-(LED2B-C)") (class "Default")
      (node (ref "LED2") (pin "4") (pinfunction "C_4") (pintype "passive"))
      (node (ref "LED3") (pin "3") (pinfunction "A_3") (pintype "passive"))
    )
    (net (code "37") (name "Net-(LED2C-C)") (class "Default")
      (node (ref "LED2") (pin "5") (pinfunction "C_5") (pintype "passive"))
      (node (ref "LED3") (pin "2") (pinfunction "A_2") (pintype "passive"))
    )
    (net (code "38") (name "Net-(LED4A-A)") (class "Default")
      (node (ref "LED4") (pin "1") (pinfunction "A_1") (pintype "passive"))
      (node (ref "R7") (pin "1") (pinfunction "1_1") (pintype "passive"))
    )
    (net (code "39") (name "Net-(LED4A-C)") (class "Default")
      (node (ref "LED4") (pin "6") (pinfunction "C_6") (pintype "passive"))
      (node (ref "LED5") (pin "1") (pinfunction "A_1") (pintype "passive"))
    )
    (net (code "40") (name "Net-(LED4B-A)") (class "Default")
      (node (ref "LED4") (pin "3") (pinfunction "A_3") (pintype "passive"))
      (node (ref "R6") (pin "1") (pinfunction "1_1") (pintype "passive"))
    )
    (net (code "41") (name "Net-(LED4B-C)") (class "Default")
      (node (ref "LED4") (pin "4") (pinfunction "C_4") (pintype "passive"))
      (node (ref "LED5") (pin "3") (pinfunction "A_3") (pintype "passive"))
    )
    (net (code "42") (name "Net-(LED4C-A)") (class "Default")
      (node (ref "LED4") (pin "2") (pinfunction "A_2") (pintype "passive"))
      (node (ref "R5") (pin "1") (pinfunction "1_1") (pintype "passive"))
    )
    (net (code "43") (name "Net-(LED4C-C)") (class "Default")
      (node (ref "LED4") (pin "5") (pinfunction "C_5") (pintype "passive"))
      (node (ref "LED5") (pin "2") (pinfunction "A_2") (pintype "passive"))
    )
    (net (code "44") (name "Net-(LED5A-C)") (class "Default")
      (node (ref "LED5") (pin "6") (pinfunction "C_6") (pintype "passive"))
      (node (ref "LED6") (pin "1") (pinfunction "A_1") (pintype "passive"))
    )
    (net (code "45") (name "Net-(LED5B-C)") (class "Default")
      (node (ref "LED5") (pin "4") (pinfunction "C_4") (pintype "passive"))
      (node (ref "LED6") (pin "3") (pinfunction "A_3") (pintype "passive"))
    )
    (net (code "46") (name "Net-(LED5C-C)") (class "Default")
      (node (ref "LED5") (pin "5") (pinfunction "C_5") (pintype "passive"))
      (node (ref "LED6") (pin "2") (pinfunction "A_2") (pintype "passive"))
    )
    (net (code "47") (name "Net-(LED7A-A)") (class "Default")
      (node (ref "LED7") (pin "1") (pinfunction "A_1") (pintype "passive"))
      (node (ref "R10") (pin "1") (pinfunction "1_1") (pintype "passive"))
    )
    (net (code "48") (name "Net-(LED7A-C)") (class "Default")
      (node (ref "LED7") (pin "6") (pinfunction "C_6") (pintype "passive"))
      (node (ref "LED8") (pin "1") (pinfunction "A_1") (pintype "passive"))
    )
    (net (code "49") (name "Net-(LED7B-A)") (class "Default")
      (node (ref "LED7") (pin "3") (pinfunction "A_3") (pintype "passive"))
      (node (ref "R9") (pin "1") (pinfunction "1_1") (pintype "passive"))
    )
    (net (code "50") (name "Net-(LED7B-C)") (class "Default")
      (node (ref "LED7") (pin "4") (pinfunction "C_4") (pintype "passive"))
      (node (ref "LED8") (pin "3") (pinfunction "A_3") (pintype "passive"))
    )
    (net (code "51") (name "Net-(LED7C-A)") (class "Default")
      (node (ref "LED7") (pin "2") (pinfunction "A_2") (pintype "passive"))
      (node (ref "R8") (pin "1") (pinfunction "1_1") (pintype "passive"))
    )
    (net (code "52") (name "Net-(LED7C-C)") (class "Default")
      (node (ref "LED7") (pin "5") (pinfunction "C_5") (pintype "passive"))
      (node (ref "LED8") (pin "2") (pinfunction "A_2") (pintype "passive"))
    )
    (net (code "53") (name "Net-(LED8A-C)") (class "Default")
      (node (ref "LED8") (pin "6") (pinfunction "C_6") (pintype "passive"))
      (node (ref "LED9") (pin "1") (pinfunction "A_1") (pintype "passive"))
    )
    (net (code "54") (name "Net-(LED8B-C)") (class "Default")
      (node (ref "LED8") (pin "4") (pinfunction "C_4") (pintype "passive"))
      (node (ref "LED9") (pin "3") (pinfunction "A_3") (pintype "passive"))
    )
    (net (code "55") (name "Net-(LED8C-C)") (class "Default")
      (node (ref "LED8") (pin "5") (pinfunction "C_5") (pintype "passive"))
      (node (ref "LED9") (pin "2") (pinfunction "A_2") (pintype "passive"))
    )
    (net (code "56") (name "Net-(LED10A-A)") (class "Default")
      (node (ref "LED10") (pin "1") (pinfunction "A_1") (pintype "passive"))
      (node (ref "R13") (pin "1") (pinfunction "1_1") (pintype "passive"))
    )
    (net (code "57") (name "Net-(LED10A-C)") (class "Default")
      (node (ref "LED10") (pin "6") (pinfunction "C_6") (pintype "passive"))
      (node (ref "LED11") (pin "1") (pinfunction "A_1") (pintype "passive"))
    )
    (net (code "58") (name "Net-(LED10B-A)") (class "Default")
      (node (ref "LED10") (pin "3") (pinfunction "A_3") (pintype "passive"))
      (node (ref "R12") (pin "1") (pinfunction "1_1") (pintype "passive"))
    )
    (net (code "59") (name "Net-(LED10B-C)") (class "Default")
      (node (ref "LED10") (pin "4") (pinfunction "C_4") (pintype "passive"))
      (node (ref "LED11") (pin "3") (pinfunction "A_3") (pintype "passive"))
    )
    (net (code "60") (name "Net-(LED10C-A)") (class "Default")
      (node (ref "LED10") (pin "2") (pinfunction "A_2") (pintype "passive"))
      (node (ref "R11") (pin "1") (pinfunction "1_1") (pintype "passive"))
    )
    (net (code "61") (name "Net-(LED10C-C)") (class "Default")
      (node (ref "LED10") (pin "5") (pinfunction "C_5") (pintype "passive"))
      (node (ref "LED11") (pin "2") (pinfunction "A_2") (pintype "passive"))
    )
    (net (code "62") (name "Net-(LED11A-C)") (class "Default")
      (node (ref "LED11") (pin "6") (pinfunction "C_6") (pintype "passive"))
      (node (ref "LED12") (pin "1") (pinfunction "A_1") (pintype "passive"))
    )
    (net (code "63") (name "Net-(LED11B-C)") (class "Default")
      (node (ref "LED11") (pin "4") (pinfunction "C_4") (pintype "passive"))
      (node (ref "LED12") (pin "3") (pinfunction "A_3") (pintype "passive"))
    )
    (net (code "64") (name "Net-(LED11C-C)") (class "Default")
      (node (ref "LED11") (pin "5") (pinfunction "C_5") (pintype "passive"))
      (node (ref "LED12") (pin "2") (pinfunction "A_2") (pintype "passive"))
    )
    (net (code "65") (name "Net-(LED12A-C)") (class "Default")
      (node (ref "LED12") (pin "4") (pinfunction "C_4") (pintype "passive"))
      (node (ref "LED12") (pin "5") (pinfunction "C_5") (pintype "passive"))
      (node (ref "LED12") (pin "6") (pinfunction "C_6") (pintype "passive"))
      (node (ref "LED30") (pin "4") (pinfunction "C_4") (pintype "passive"))
      (node (ref "LED30") (pin "5") (pinfunction "C_5") (pintype "passive"))
      (node (ref "LED30") (pin "6") (pinfunction "C_6") (pintype "passive"))
      (node (ref "LED69") (pin "4") (pinfunction "C_4") (pintype "passive"))
      (node (ref "LED69") (pin "5") (pinfunction "C_5") (pintype "passive"))
      (node (ref "LED69") (pin "6") (pinfunction "C_6") (pintype "passive"))
      (node (ref "U2") (pin "13") (pinfunction "4C_13") (pintype "output"))
    )
    (net (code "66") (name "Net-(LED13A-A)") (class "Default")
      (node (ref "LED13") (pin "1") (pinfunction "A_1") (pintype "passive"))
      (node (ref "R16") (pin "1") (pinfunction "1_1") (pintype "passive"))
    )
    (net (code "67") (name "Net-(LED13A-C)") (class "Default")
      (node (ref "LED13") (pin "6") (pinfunction "C_6") (pintype "passive"))
      (node (ref "LED14") (pin "1") (pinfunction "A_1") (pintype "passive"))
    )
    (net (code "68") (name "Net-(LED13B-A)") (class "Default")
      (node (ref "LED13") (pin "3") (pinfunction "A_3") (pintype "passive"))
      (node (ref "R15") (pin "1") (pinfunction "1_1") (pintype "passive"))
    )
    (net (code "69") (name "Net-(LED13B-C)") (class "Default")
      (node (ref "LED13") (pin "4") (pinfunction "C_4") (pintype "passive"))
      (node (ref "LED14") (pin "3") (pinfunction "A_3") (pintype "passive"))
    )
    (net (code "70") (name "Net-(LED13C-A)") (class "Default")
      (node (ref "LED13") (pin "2") (pinfunction "A_2") (pintype "passive"))
      (node (ref "R14") (pin "1") (pinfunction "1_1") (pintype "passive"))
    )
    (net (code "71") (name "Net-(LED13C-C)") (class "Default")
      (node (ref "LED13") (pin "5") (pinfunction "C_5") (pintype "passive"))
      (node (ref "LED14") (pin "2") (pinfunction "A_2") (pintype "passive"))
    )
    (net (code "72") (name "Net-(LED14A-C)") (class "Default")
      (node (ref "LED14") (pin "6") (pinfunction "C_6") (pintype "passive"))
      (node (ref "LED15") (pin "1") (pinfunction "A_1") (pintype "passive"))
    )
    (net (code "73") (name "Net-(LED14B-C)") (class "Default")
      (node (ref "LED14") (pin "4") (pinfunction "C_4") (pintype "passive"))
      (node (ref "LED15") (pin "3") (pinfunction "A_3") (pintype "passive"))
    )
    (net (code "74") (name "Net-(LED14C-C)") (class "Default")
      (node (ref "LED14") (pin "5") (pinfunction "C_5") (pintype "passive"))
      (node (ref "LED15") (pin "2") (pinfunction "A_2") (pintype "passive"))
    )
    (net (code "75") (name "Net-(LED15A-C)") (class "Default")
      (node (ref "LED15") (pin "4") (pinfunction "C_4") (pintype "passive"))
      (node (ref "LED15") (pin "5") (pinfunction "C_5") (pintype "passive"))
      (node (ref "LED15") (pin "6") (pinfunction "C_6") (pintype "passive"))
      (node (ref "LED33") (pin "4") (pinfunction "C_4") (pintype "passive"))
      (node (ref "LED33") (pin "5") (pinfunction "C_5") (pintype "passive"))
      (node (ref "LED33") (pin "6") (pinfunction "C_6") (pintype "passive"))
      (node (ref "LED72") (pin "4") (pinfunction "C_4") (pintype "passive"))
      (node (ref "LED72") (pin "5") (pinfunction "C_5") (pintype "passive"))
      (node (ref "LED72") (pin "6") (pinfunction "C_6") (pintype "passive"))
      (node (ref "U2") (pin "14") (pinfunction "3C_14") (pintype "output"))
    )
    (net (code "76") (name "Net-(LED16A-A)") (class "Default")
      (node (ref "LED16") (pin "1") (pinfunction "A_1") (pintype "passive"))
      (node (ref "R19") (pin "1") (pinfunction "1_1") (pintype "passive"))
    )
    (net (code "77") (name "Net-(LED16A-C)") (class "Default")
      (node (ref "LED16") (pin "6") (pinfunction "C_6") (pintype "passive"))
      (node (ref "LED17") (pin "1") (pinfunction "A_1") (pintype "passive"))
    )
    (net (code "78") (name "Net-(LED16B-A)") (class "Default")
      (node (ref "LED16") (pin "3") (pinfunction "A_3") (pintype "passive"))
      (node (ref "R18") (pin "1") (pinfunction "1_1") (pintype "passive"))
    )
    (net (code "79") (name "Net-(LED16B-C)") (class "Default")
      (node (ref "LED16") (pin "4") (pinfunction "C_4") (pintype "passive"))
      (node (ref "LED17") (pin "3") (pinfunction "A_3") (pintype "passive"))
    )
    (net (code "80") (name "Net-(LED16C-A)") (class "Default")
      (node (ref "LED16") (pin "2") (pinfunction "A_2") (pintype "passive"))
      (node (ref "R17") (pin "1") (pinfunction "1_1") (pintype "passive"))
    )
    (net (code "81") (name "Net-(LED16C-C)") (class "Default")
      (node (ref "LED16") (pin "5") (pinfunction "C_5") (pintype "passive"))
      (node (ref "LED17") (pin "2") (pinfunction "A_2") (pintype "passive"))
    )
    (net (code "82") (name "Net-(LED17A-C)") (class "Default")
      (node (ref "LED17") (pin "6") (pinfunction "C_6") (pintype "passive"))
      (node (ref "LED18") (pin "1") (pinfunction "A_1") (pintype "passive"))
    )
    (net (code "83") (name "Net-(LED17B-C)") (class "Default")
      (node (ref "LED17") (pin "4") (pinfunction "C_4") (pintype "passive"))
      (node (ref "LED18") (pin "3") (pinfunction "A_3") (pintype "passive"))
    )
    (net (code "84") (name "Net-(LED17C-C)") (class "Default")
      (node (ref "LED17") (pin "5") (pinfunction "C_5") (pintype "passive"))
      (node (ref "LED18") (pin "2") (pinfunction "A_2") (pintype "passive"))
    )
    (net (code "85") (name "Net-(LED18A-C)") (class "Default")
      (node (ref "LED18") (pin "4") (pinfunction "C_4") (pintype "passive"))
      (node (ref "LED18") (pin "5") (pinfunction "C_5") (pintype "passive"))
      (node (ref "LED18") (pin "6") (pinfunction "C_6") (pintype "passive"))
      (node (ref "LED36") (pin "4") (pinfunction "C_4") (pintype "passive"))
      (node (ref "LED36") (pin "5") (pinfunction "C_5") (pintype "passive"))
      (node (ref "LED36") (pin "6") (pinfunction "C_6") (pintype "passive"))
      (node (ref "LED75") (pin "4") (pinfunction "C_4") (pintype "passive"))
      (node (ref "LED75") (pin "5") (pinfunction "C_5") (pintype "passive"))
      (node (ref "LED75") (pin "6") (pinfunction "C_6") (pintype "passive"))
      (node (ref "U2") (pin "15") (pinfunction "2C_15") (pintype "output"))
    )
    (net (code "86") (name "Net-(LED19A-A)") (class "Default")
      (node (ref "LED19") (pin "1") (pinfunction "A_1") (pintype "passive"))
      (node (ref "R22") (pin "1") (pinfunction "1_1") (pintype "passive"))
    )
    (net (code "87") (name "Net-(LED19A-C)") (class "Default")
      (node (ref "LED19") (pin "6") (pinfunction "C_6") (pintype "passive"))
      (node (ref "LED20") (pin "1") (pinfunction "A_1") (pintype "passive"))
    )
    (net (code "88") (name "Net-(LED19B-A)") (class "Default")
      (node (ref "LED19") (pin "3") (pinfunction "A_3") (pintype "passive"))
      (node (ref "R21") (pin "1") (pinfunction "1_1") (pintype "passive"))
    )
    (net (code "89") (name "Net-(LED19B-C)") (class "Default")
      (node (ref "LED19") (pin "4") (pinfunction "C_4") (pintype "passive"))
      (node (ref "LED20") (pin "3") (pinfunction "A_3") (pintype "passive"))
    )
    (net (code "90") (name "Net-(LED19C-A)") (class "Default")
      (node (ref "LED19") (pin "2") (pinfunction "A_2") (pintype "passive"))
      (node (ref "R20") (pin "1") (pinfunction "1_1") (pintype "passive"))
    )
    (net (code "91") (name "Net-(LED19C-C)") (class "Default")
      (node (ref "LED19") (pin "5") (pinfunction "C_5") (pintype "passive"))
      (node (ref "LED20") (pin "2") (pinfunction "A_2") (pintype "passive"))
    )
    (net (code "92") (name "Net-(LED20A-C)") (class "Default")
      (node (ref "LED20") (pin "6") (pinfunction "C_6") (pintype "passive"))
      (node (ref "LED21") (pin "1") (pinfunction "A_1") (pintype "passive"))
    )
    (net (code "93") (name "Net-(LED20B-C)") (class "Default")
      (node (ref "LED20") (pin "4") (pinfunction "C_4") (pintype "passive"))
      (node (ref "LED21") (pin "3") (pinfunction "A_3") (pintype "passive"))
    )
    (net (code "94") (name "Net-(LED20C-C)") (class "Default")
      (node (ref "LED20") (pin "5") (pinfunction "C_5") (pintype "passive"))
      (node (ref "LED21") (pin "2") (pinfunction "A_2") (pintype "passive"))
    )
    (net (code "95") (name "Net-(LED21A-C)") (class "Default")
      (node (ref "LED21") (pin "4") (pinfunction "C_4") (pintype "passive"))
      (node (ref "LED21") (pin "5") (pinfunction "C_5") (pintype "passive"))
      (node (ref "LED21") (pin "6") (pinfunction "C_6") (pintype "passive"))
      (node (ref "LED3") (pin "4") (pinfunction "C_4") (pintype "passive"))
      (node (ref "LED3") (pin "5") (pinfunction "C_5") (pintype "passive"))
      (node (ref "LED3") (pin "6") (pinfunction "C_6") (pintype "passive"))
      (node (ref "LED60") (pin "4") (pinfunction "C_4") (pintype "passive"))
      (node (ref "LED60") (pin "5") (pinfunction "C_5") (pintype "passive"))
      (node (ref "LED60") (pin "6") (pinfunction "C_6") (pintype "passive"))
      (node (ref "U2") (pin "10") (pinfunction "7C_10") (pintype "output"))
    )
    (net (code "96") (name "Net-(LED22A-A)") (class "Default")
      (node (ref "LED22") (pin "1") (pinfunction "A_1") (pintype "passive"))
      (node (ref "R25") (pin "1") (pinfunction "1_1") (pintype "passive"))
    )
    (net (code "97") (name "Net-(LED22A-C)") (class "Default")
      (node (ref "LED22") (pin "6") (pinfunction "C_6") (pintype "passive"))
      (node (ref "LED23") (pin "1") (pinfunction "A_1") (pintype "passive"))
    )
    (net (code "98") (name "Net-(LED22B-A)") (class "Default")
      (node (ref "LED22") (pin "3") (pinfunction "A_3") (pintype "passive"))
      (node (ref "R24") (pin "1") (pinfunction "1_1") (pintype "passive"))
    )
    (net (code "99") (name "Net-(LED22B-C)") (class "Default")
      (node (ref "LED22") (pin "4") (pinfunction "C_4") (pintype "passive"))
      (node (ref "LED23") (pin "3") (pinfunction "A_3") (pintype "passive"))
    )
    (net (code "100") (name "Net-(LED22C-A)") (class "Default")
      (node (ref "LED22") (pin "2") (pinfunction "A_2") (pintype "passive"))
      (node (ref "R23") (pin "1") (pinfunction "1_1") (pintype "passive"))
    )
    (net (code "101") (name "Net-(LED22C-C)") (class "Default")
      (node (ref "LED22") (pin "5") (pinfunction "C_5") (pintype "passive"))
      (node (ref "LED23") (pin "2") (pinfunction "A_2") (pintype "passive"))
    )
    (net (code "102") (name "Net-(LED23A-C)") (class "Default")
      (node (ref "LED23") (pin "6") (pinfunction "C_6") (pintype "passive"))
      (node (ref "LED24") (pin "1") (pinfunction "A_1") (pintype "passive"))
    )
    (net (code "103") (name "Net-(LED23B-C)") (class "Default")
      (node (ref "LED23") (pin "4") (pinfunction "C_4") (pintype "passive"))
      (node (ref "LED24") (pin "3") (pinfunction "A_3") (pintype "passive"))
    )
    (net (code "104") (name "Net-(LED23C-C)") (class "Default")
      (node (ref "LED23") (pin "5") (pinfunction "C_5") (pintype "passive"))
      (node (ref "LED24") (pin "2") (pinfunction "A_2") (pintype "passive"))
    )
    (net (code "105") (name "Net-(LED24A-C)") (class "Default")
      (node (ref "LED24") (pin "4") (pinfunction "C_4") (pintype "passive"))
      (node (ref "LED24") (pin "5") (pinfunction "C_5") (pintype "passive"))
      (node (ref "LED24") (pin "6") (pinfunction "C_6") (pintype "passive"))
      (node (ref "LED6") (pin "4") (pinfunction "C_4") (pintype "passive"))
      (node (ref "LED6") (pin "5") (pinfunction "C_5") (pintype "passive"))
      (node (ref "LED6") (pin "6") (pinfunction "C_6") (pintype "passive"))
      (node (ref "LED63") (pin "4") (pinfunction "C_4") (pintype "passive"))
      (node (ref "LED63") (pin "5") (pinfunction "C_5") (pintype "passive"))
      (node (ref "LED63") (pin "6") (pinfunction "C_6") (pintype "passive"))
      (node (ref "U2") (pin "11") (pinfunction "6C_11") (pintype "output"))
    )
    (net (code "106") (name "Net-(LED25A-A)") (class "Default")
      (node (ref "LED25") (pin "1") (pinfunction "A_1") (pintype "passive"))
      (node (ref "R28") (pin "1") (pinfunction "1_1") (pintype "passive"))
    )
    (net (code "107") (name "Net-(LED25A-C)") (class "Default")
      (node (ref "LED25") (pin "6") (pinfunction "C_6") (pintype "passive"))
      (node (ref "LED26") (pin "1") (pinfunction "A_1") (pintype "passive"))
    )
    (net (code "108") (name "Net-(LED25B-A)") (class "Default")
      (node (ref "LED25") (pin "3") (pinfunction "A_3") (pintype "passive"))
      (node (ref "R27") (pin "1") (pinfunction "1_1") (pintype "passive"))
    )
    (net (code "109") (name "Net-(LED25B-C)") (class "Default")
      (node (ref "LED25") (pin "4") (pinfunction "C_4") (pintype "passive"))
      (node (ref "LED26") (pin "3") (pinfunction "A_3") (pintype "passive"))
    )
    (net (code "110") (name "Net-(LED25C-A)") (class "Default")
      (node (ref "LED25") (pin "2") (pinfunction "A_2") (pintype "passive"))
      (node (ref "R26") (pin "1") (pinfunction "1_1") (pintype "passive"))
    )
    (net (code "111") (name "Net-(LED25C-C)") (class "Default")
      (node (ref "LED25") (pin "5") (pinfunction "C_5") (pintype "passive"))
      (node (ref "LED26") (pin "2") (pinfunction "A_2") (pintype "passive"))
    )
    (net (code "112") (name "Net-(LED26A-C)") (class "Default")
      (node (ref "LED26") (pin "6") (pinfunction "C_6") (pintype "passive"))
      (node (ref "LED27") (pin "1") (pinfunction "A_1") (pintype "passive"))
    )
    (net (code "113") (name "Net-(LED26B-C)") (class "Default")
      (node (ref "LED26") (pin "4") (pinfunction "C_4") (pintype "passive"))
      (node (ref "LED27") (pin "3") (pinfunction "A_3") (pintype "passive"))
    )
    (net (code "114") (name "Net-(LED26C-C)") (class "Default")
      (node (ref "LED26") (pin "5") (pinfunction "C_5") (pintype "passive"))
      (node (ref "LED27") (pin "2") (pinfunction "A_2") (pintype "passive"))
    )
    (net (code "115") (name "Net-(LED27A-C)") (class "Default")
      (node (ref "LED27") (pin "4") (pinfunction "C_4") (pintype "passive"))
      (node (ref "LED27") (pin "5") (pinfunction "C_5") (pintype "passive"))
      (node (ref "LED27") (pin "6") (pinfunction "C_6") (pintype "passive"))
      (node (ref "LED66") (pin "4") (pinfunction "C_4") (pintype "passive"))
      (node (ref "LED66") (pin "5") (pinfunction "C_5") (pintype "passive"))
      (node (ref "LED66") (pin "6") (pinfunction "C_6") (pintype "passive"))
      (node (ref "LED9") (pin "4") (pinfunction "C_4") (pintype "passive"))
      (node (ref "LED9") (pin "5") (pinfunction "C_5") (pintype "passive"))
      (node (ref "LED9") (pin "6") (pinfunction "C_6") (pintype "passive"))
      (node (ref "U2") (pin "12") (pinfunction "5C_12") (pintype "output"))
    )
    (net (code "116") (name "Net-(LED28A-A)") (class "Default")
      (node (ref "LED28") (pin "1") (pinfunction "A_1") (pintype "passive"))
      (node (ref "R31") (pin "1") (pinfunction "1_1") (pintype "passive"))
    )
    (net (code "117") (name "Net-(LED28A-C)") (class "Default")
      (node (ref "LED28") (pin "6") (pinfunction "C_6") (pintype "passive"))
      (node (ref "LED29") (pin "1") (pinfunction "A_1") (pintype "passive"))
    )
    (net (code "118") (name "Net-(LED28B-A)") (class "Default")
      (node (ref "LED28") (pin "3") (pinfunction "A_3") (pintype "passive"))
      (node (ref "R30") (pin "1") (pinfunction "1_1") (pintype "passive"))
    )
    (net (code "119") (name "Net-(LED28B-C)") (class "Default")
      (node (ref "LED28") (pin "4") (pinfunction "C_4") (pintype "passive"))
      (node (ref "LED29") (pin "3") (pinfunction "A_3") (pintype "passive"))
    )
    (net (code "120") (name "Net-(LED28C-A)") (class "Default")
      (node (ref "LED28") (pin "2") (pinfunction "A_2") (pintype "passive"))
      (node (ref "R29") (pin "1") (pinfunction "1_1") (pintype "passive"))
    )
    (net (code "121") (name "Net-(LED28C-C)") (class "Default")
      (node (ref "LED28") (pin "5") (pinfunction "C_5") (pintype "passive"))
      (node (ref "LED29") (pin "2") (pinfunction "A_2") (pintype "passive"))
    )
    (net (code "122") (name "Net-(LED29A-C)") (class "Default")
      (node (ref "LED29") (pin "6") (pinfunction "C_6") (pintype "passive"))
      (node (ref "LED30") (pin "1") (pinfunction "A_1") (pintype "passive"))
    )
    (net (code "123") (name "Net-(LED29B-C)") (class "Default")
      (node (ref "LED29") (pin "4") (pinfunction "C_4") (pintype "passive"))
      (node (ref "LED30") (pin "3") (pinfunction "A_3") (pintype "passive"))
    )
    (net (code "124") (name "Net-(LED29C-C)") (class "Default")
      (node (ref "LED29") (pin "5") (pinfunction "C_5") (pintype "passive"))
      (node (ref "LED30") (pin "2") (pinfunction "A_2") (pintype "passive"))
    )
    (net (code "125") (name "Net-(LED31A-A)") (class "Default")
      (node (ref "LED31") (pin "1") (pinfunction "A_1") (pintype "passive"))
      (node (ref "R34") (pin "1") (pinfunction "1_1") (pintype "passive"))
    )
    (net (code "126") (name "Net-(LED31A-C)") (class "Default")
      (node (ref "LED31") (pin "6") (pinfunction "C_6") (pintype "passive"))
      (node (ref "LED32") (pin "1") (pinfunction "A_1") (pintype "passive"))
    )
    (net (code "127") (name "Net-(LED31B-A)") (class "Default")
      (node (ref "LED31") (pin "3") (pinfunction "A_3") (pintype "passive"))
      (node (ref "R33") (pin "1") (pinfunction "1_1") (pintype "passive"))
    )
    (net (code "128") (name "Net-(LED31B-C)") (class "Default")
      (node (ref "LED31") (pin "4") (pinfunction "C_4") (pintype "passive"))
      (node (ref "LED32") (pin "3") (pinfunction "A_3") (pintype "passive"))
    )
    (net (code "129") (name "Net-(LED31C-A)") (class "Default")
      (node (ref "LED31") (pin "2") (pinfunction "A_2") (pintype "passive"))
      (node (ref "R32") (pin "1") (pinfunction "1_1") (pintype "passive"))
    )
    (net (code "130") (name "Net-(LED31C-C)") (class "Default")
      (node (ref "LED31") (pin "5") (pinfunction "C_5") (pintype "passive"))
      (node (ref "LED32") (pin "2") (pinfunction "A_2") (pintype "passive"))
    )
    (net (code "131") (name "Net-(LED32A-C)") (class "Default")
      (node (ref "LED32") (pin "6") (pinfunction "C_6") (pintype "passive"))
      (node (ref "LED33") (pin "1") (pinfunction "A_1") (pintype "passive"))
    )
    (net (code "132") (name "Net-(LED32B-C)") (class "Default")
      (node (ref "LED32") (pin "4") (pinfunction "C_4") (pintype "passive"))
      (node (ref "LED33") (pin "3") (pinfunction "A_3") (pintype "passive"))
    )
    (net (code "133") (name "Net-(LED32C-C)") (class "Default")
      (node (ref "LED32") (pin "5") (pinfunction "C_5") (pintype "passive"))
      (node (ref "LED33") (pin "2") (pinfunction "A_2") (pintype "passive"))
    )
    (net (code "134") (name "Net-(LED34A-A)") (class "Default")
      (node (ref "LED34") (pin "1") (pinfunction "A_1") (pintype "passive"))
      (node (ref "R37") (pin "1") (pinfunction "1_1") (pintype "passive"))
    )
    (net (code "135") (name "Net-(LED34A-C)") (class "Default")
      (node (ref "LED34") (pin "6") (pinfunction "C_6") (pintype "passive"))
      (node (ref "LED35") (pin "1") (pinfunction "A_1") (pintype "passive"))
    )
    (net (code "136") (name "Net-(LED34B-A)") (class "Default")
      (node (ref "LED34") (pin "3") (pinfunction "A_3") (pintype "passive"))
      (node (ref "R36") (pin "1") (pinfunction "1_1") (pintype "passive"))
    )
    (net (code "137") (name "Net-(LED34B-C)") (class "Default")
      (node (ref "LED34") (pin "4") (pinfunction "C_4") (pintype "passive"))
      (node (ref "LED35") (pin "3") (pinfunction "A_3") (pintype "passive"))
    )
    (net (code "138") (name "Net-(LED34C-A)") (class "Default")
      (node (ref "LED34") (pin "2") (pinfunction "A_2") (pintype "passive"))
      (node (ref "R35") (pin "1") (pinfunction "1_1") (pintype "passive"))
    )
    (net (code "139") (name "Net-(LED34C-C)") (class "Default")
      (node (ref "LED34") (pin "5") (pinfunction "C_5") (pintype "passive"))
      (node (ref "LED35") (pin "2") (pinfunction "A_2") (pintype "passive"))
    )
    (net (code "140") (name "Net-(LED35A-C)") (class "Default")
      (node (ref "LED35") (pin "6") (pinfunction "C_6") (pintype "passive"))
      (node (ref "LED36") (pin "1") (pinfunction "A_1") (pintype "passive"))
    )
    (net (code "141") (name "Net-(LED35B-C)") (class "Default")
      (node (ref "LED35") (pin "4") (pinfunction "C_4") (pintype "passive"))
      (node (ref "LED36") (pin "3") (pinfunction "A_3") (pintype "passive"))
    )
    (net (code "142") (name "Net-(LED35C-C)") (class "Default")
      (node (ref "LED35") (pin "5") (pinfunction "C_5") (pintype "passive"))
      (node (ref "LED36") (pin "2") (pinfunction "A_2") (pintype "passive"))
    )
    (net (code "143") (name "Net-(LED37A-A)") (class "Default")
      (node (ref "LED37") (pin "1") (pinfunction "A_1") (pintype "passive"))
      (node (ref "R40") (pin "1") (pinfunction "1_1") (pintype "passive"))
    )
    (net (code "144") (name "Net-(LED37A-C)") (class "Default")
      (node (ref "LED37") (pin "6") (pinfunction "C_6") (pintype "passive"))
      (node (ref "LED38") (pin "1") (pinfunction "A_1") (pintype "passive"))
    )
    (net (code "145") (name "Net-(LED37B-A)") (class "Default")
      (node (ref "LED37") (pin "3") (pinfunction "A_3") (pintype "passive"))
      (node (ref "R39") (pin "1") (pinfunction "1_1") (pintype "passive"))
    )
    (net (code "146") (name "Net-(LED37B-C)") (class "Default")
      (node (ref "LED37") (pin "4") (pinfunction "C_4") (pintype "passive"))
      (node (ref "LED38") (pin "3") (pinfunction "A_3") (pintype "passive"))
    )
    (net (code "147") (name "Net-(LED37C-A)") (class "Default")
      (node (ref "LED37") (pin "2") (pinfunction "A_2") (pintype "passive"))
      (node (ref "R38") (pin "1") (pinfunction "1_1") (pintype "passive"))
    )
    (net (code "148") (name "Net-(LED37C-C)") (class "Default")
      (node (ref "LED37") (pin "5") (pinfunction "C_5") (pintype "passive"))
      (node (ref "LED38") (pin "2") (pinfunction "A_2") (pintype "passive"))
    )
    (net (code "149") (name "Net-(LED38A-C)") (class "Default")
      (node (ref "LED38") (pin "6") (pinfunction "C_6") (pintype "passive"))
      (node (ref "LED39") (pin "1") (pinfunction "A_1") (pintype "passive"))
    )
    (net (code "150") (name "Net-(LED38B-C)") (class "Default")
      (node (ref "LED38") (pin "4") (pinfunction "C_4") (pintype "passive"))
      (node (ref "LED39") (pin "3") (pinfunction "A_3") (pintype "passive"))
    )
    (net (code "151") (name "Net-(LED38C-C)") (class "Default")
      (node (ref "LED38") (pin "5") (pinfunction "C_5") (pintype "passive"))
      (node (ref "LED39") (pin "2") (pinfunction "A_2") (pintype "passive"))
    )
    (net (code "152") (name "Net-(LED39A-C)") (class "Default")
      (node (ref "LED39") (pin "4") (pinfunction "C_4") (pintype "passive"))
      (node (ref "LED39") (pin "5") (pinfunction "C_5") (pintype "passive"))
      (node (ref "LED39") (pin "6") (pinfunction "C_6") (pintype "passive"))
      (node (ref "U2") (pin "16") (pinfunction "1C_16") (pintype "output"))
    )
    (net (code "153") (name "Net-(LED58A-A)") (class "Default")
      (node (ref "LED58") (pin "1") (pinfunction "A_1") (pintype "passive"))
      (node (ref "R61") (pin "1") (pinfunction "1_1") (pintype "passive"))
    )
    (net (code "154") (name "Net-(LED58A-C)") (class "Default")
      (node (ref "LED58") (pin "6") (pinfunction "C_6") (pintype "passive"))
      (node (ref "LED59") (pin "1") (pinfunction "A_1") (pintype "passive"))
    )
    (net (code "155") (name "Net-(LED58B-A)") (class "Default")
      (node (ref "LED58") (pin "3") (pinfunction "A_3") (pintype "passive"))
      (node (ref "R60") (pin "1") (pinfunction "1_1") (pintype "passive"))
    )
    (net (code "156") (name "Net-(LED58B-C)") (class "Default")
      (node (ref "LED58") (pin "4") (pinfunction "C_4") (pintype "passive"))
      (node (ref "LED59") (pin "3") (pinfunction "A_3") (pintype "passive"))
    )
    (net (code "157") (name "Net-(LED58C-A)") (class "Default")
      (node (ref "LED58") (pin "2") (pinfunction "A_2") (pintype "passive"))
      (node (ref "R59") (pin "1") (pinfunction "1_1") (pintype "passive"))
    )
    (net (code "158") (name "Net-(LED58C-C)") (class "Default")
      (node (ref "LED58") (pin "5") (pinfunction "C_5") (pintype "passive"))
      (node (ref "LED59") (pin "2") (pinfunction "A_2") (pintype "passive"))
    )
    (net (code "159") (name "Net-(LED59A-C)") (class "Default")
      (node (ref "LED59") (pin "6") (pinfunction "C_6") (pintype "passive"))
      (node (ref "LED60") (pin "1") (pinfunction "A_1") (pintype "passive"))
    )
    (net (code "160") (name "Net-(LED59B-C)") (class "Default")
      (node (ref "LED59") (pin "4") (pinfunction "C_4") (pintype "passive"))
      (node (ref "LED60") (pin "3") (pinfunction "A_3") (pintype "passive"))
    )
    (net (code "161") (name "Net-(LED59C-C)") (class "Default")
      (node (ref "LED59") (pin "5") (pinfunction "C_5") (pintype "passive"))
      (node (ref "LED60") (pin "2") (pinfunction "A_2") (pintype "passive"))
    )
    (net (code "162") (name "Net-(LED61A-A)") (class "Default")
      (node (ref "LED61") (pin "1") (pinfunction "A_1") (pintype "passive"))
      (node (ref "R64") (pin "1") (pinfunction "1_1") (pintype "passive"))
    )
    (net (code "163") (name "Net-(LED61A-C)") (class "Default")
      (node (ref "LED61") (pin "6") (pinfunction "C_6") (pintype "passive"))
      (node (ref "LED62") (pin "1") (pinfunction "A_1") (pintype "passive"))
    )
    (net (code "164") (name "Net-(LED61B-A)") (class "Default")
      (node (ref "LED61") (pin "3") (pinfunction "A_3") (pintype "passive"))
      (node (ref "R63") (pin "1") (pinfunction "1_1") (pintype "passive"))
    )
    (net (code "165") (name "Net-(LED61B-C)") (class "Default")
      (node (ref "LED61") (pin "4") (pinfunction "C_4") (pintype "passive"))
      (node (ref "LED62") (pin "3") (pinfunction "A_3") (pintype "passive"))
    )
    (net (code "166") (name "Net-(LED61C-A)") (class "Default")
      (node (ref "LED61") (pin "2") (pinfunction "A_2") (pintype "passive"))
      (node (ref "R62") (pin "1") (pinfunction "1_1") (pintype "passive"))
    )
    (net (code "167") (name "Net-(LED61C-C)") (class "Default")
      (node (ref "LED61") (pin "5") (pinfunction "C_5") (pintype "passive"))
      (node (ref "LED62") (pin "2") (pinfunction "A_2") (pintype "passive"))
    )
    (net (code "168") (name "Net-(LED62A-C)") (class "Default")
      (node (ref "LED62") (pin "6") (pinfunction "C_6") (pintype "passive"))
      (node (ref "LED63") (pin "1") (pinfunction "A_1") (pintype "passive"))
    )
    (net (code "169") (name "Net-(LED62B-C)") (class "Default")
      (node (ref "LED62") (pin "4") (pinfunction "C_4") (pintype "passive"))
      (node (ref "LED63") (pin "3") (pinfunction "A_3") (pintype "passive"))
    )
    (net (code "170") (name "Net-(LED62C-C)") (class "Default")
      (node (ref "LED62") (pin "5") (pinfunction "C_5") (pintype "passive"))
      (node (ref "LED63") (pin "2") (pinfunction "A_2") (pintype "passive"))
    )
    (net (code "171") (name "Net-(LED64A-A)") (class "Default")
      (node (ref "LED64") (pin "1") (pinfunction "A_1") (pintype "passive"))
      (node (ref "R67") (pin "1") (pinfunction "1_1") (pintype "passive"))
    )
    (net (code "172") (name "Net-(LED64A-C)") (class "Default")
      (node (ref "LED64") (pin "6") (pinfunction "C_6") (pintype "passive"))
      (node (ref "LED65") (pin "1") (pinfunction "A_1") (pintype "passive"))
    )
    (net (code "173") (name "Net-(LED64B-A)") (class "Default")
      (node (ref "LED64") (pin "3") (pinfunction "A_3") (pintype "passive"))
      (node (ref "R66") (pin "1") (pinfunction "1_1") (pintype "passive"))
    )
    (net (code "174") (name "Net-(LED64B-C)") (class "Default")
      (node (ref "LED64") (pin "4") (pinfunction "C_4") (pintype "passive"))
      (node (ref "LED65") (pin "3") (pinfunction "A_3") (pintype "passive"))
    )
    (net (code "175") (name "Net-(LED64C-A)") (class "Default")
      (node (ref "LED64") (pin "2") (pinfunction "A_2") (pintype "passive"))
      (node (ref "R65") (pin "1") (pinfunction "1_1") (pintype "passive"))
    )
    (net (code "176") (name "Net-(LED64C-C)") (class "Default")
      (node (ref "LED64") (pin "5") (pinfunction "C_5") (pintype "passive"))
      (node (ref "LED65") (pin "2") (pinfunction "A_2") (pintype "passive"))
    )
    (net (code "177") (name "Net-(LED65A-C)") (class "Default")
      (node (ref "LED65") (pin "6") (pinfunction "C_6") (pintype "passive"))
      (node (ref "LED66") (pin "1") (pinfunction "A_1") (pintype "passive"))
    )
    (net (code "178") (name "Net-(LED65B-C)") (class "Default")
      (node (ref "LED65") (pin "4") (pinfunction "C_4") (pintype "passive"))
      (node (ref "LED66") (pin "3") (pinfunction "A_3") (pintype "passive"))
    )
    (net (code "179") (name "Net-(LED65C-C)") (class "Default")
      (node (ref "LED65") (pin "5") (pinfunction "C_5") (pintype "passive"))
      (node (ref "LED66") (pin "2") (pinfunction "A_2") (pintype "passive"))
    )
    (net (code "180") (name "Net-(LED67A-A)") (class "Default")
      (node (ref "LED67") (pin "1") (pinfunction "A_1") (pintype "passive"))
      (node (ref "R70") (pin "1") (pinfunction "1_1") (pintype "passive"))
    )
    (net (code "181") (name "Net-(LED67A-C)") (class "Default")
      (node (ref "LED67") (pin "6") (pinfunction "C_6") (pintype "passive"))
      (node (ref "LED68") (pin "1") (pinfunction "A_1") (pintype "passive"))
    )
    (net (code "182") (name "Net-(LED67B-A)") (class "Default")
      (node (ref "LED67") (pin "3") (pinfunction "A_3") (pintype "passive"))
      (node (ref "R69") (pin "1") (pinfunction "1_1") (pintype "passive"))
    )
    (net (code "183") (name "Net-(LED67B-C)") (class "Default")
      (node (ref "LED67") (pin "4") (pinfunction "C_4") (pintype "passive"))
      (node (ref "LED68") (pin "3") (pinfunction "A_3") (pintype "passive"))
    )
    (net (code "184") (name "Net-(LED67C-A)") (class "Default")
      (node (ref "LED67") (pin "2") (pinfunction "A_2") (pintype "passive"))
      (node (ref "R68") (pin "1") (pinfunction "1_1") (pintype "passive"))
    )
    (net (code "185") (name "Net-(LED67C-C)") (class "Default")
      (node (ref "LED67") (pin "5") (pinfunction "C_5") (pintype "passive"))
      (node (ref "LED68") (pin "2") (pinfunction "A_2") (pintype "passive"))
    )
    (net (code "186") (name "Net-(LED68A-C)") (class "Default")
      (node (ref "LED68") (pin "6") (pinfunction "C_6") (pintype "passive"))
      (node (ref "LED69") (pin "1") (pinfunction "A_1") (pintype "passive"))
    )
    (net (code "187") (name "Net-(LED68B-C)") (class "Default")
      (node (ref "LED68") (pin "4") (pinfunction "C_4") (pintype "passive"))
      (node (ref "LED69") (pin "3") (pinfunction "A_3") (pintype "passive"))
    )
    (net (code "188") (name "Net-(LED68C-C)") (class "Default")
      (node (ref "LED68") (pin "5") (pinfunction "C_5") (pintype "passive"))
      (node (ref "LED69") (pin "2") (pinfunction "A_2") (pintype "passive"))
    )
    (net (code "189") (name "Net-(LED70A-A)") (class "Default")
      (node (ref "LED70") (pin "1") (pinfunction "A_1") (pintype "passive"))
      (node (ref "R73") (pin "1") (pinfunction "1_1") (pintype "passive"))
    )
    (net (code "190") (name "Net-(LED70A-C)") (class "Default")
      (node (ref "LED70") (pin "6") (pinfunction "C_6") (pintype "passive"))
      (node (ref "LED71") (pin "1") (pinfunction "A_1") (pintype "passive"))
    )
    (net (code "191") (name "Net-(LED70B-A)") (class "Default")
      (node (ref "LED70") (pin "3") (pinfunction "A_3") (pintype "passive"))
      (node (ref "R72") (pin "1") (pinfunction "1_1") (pintype "passive"))
    )
    (net (code "192") (name "Net-(LED70B-C)") (class "Default")
      (node (ref "LED70") (pin "4") (pinfunction "C_4") (pintype "passive"))
      (node (ref "LED71") (pin "3") (pinfunction "A_3") (pintype "passive"))
    )
    (net (code "193") (name "Net-(LED70C-A)") (class "Default")
      (node (ref "LED70") (pin "2") (pinfunction "A_2") (pintype "passive"))
      (node (ref "R71") (pin "1") (pinfunction "1_1") (pintype "passive"))
    )
    (net (code "194") (name "Net-(LED70C-C)") (class "Default")
      (node (ref "LED70") (pin "5") (pinfunction "C_5") (pintype "passive"))
      (node (ref "LED71") (pin "2") (pinfunction "A_2") (pintype "passive"))
    )
    (net (code "195") (name "Net-(LED71A-C)") (class "Default")
      (node (ref "LED71") (pin "6") (pinfunction "C_6") (pintype "passive"))
      (node (ref "LED72") (pin "1") (pinfunction "A_1") (pintype "passive"))
    )
    (net (code "196") (name "Net-(LED71B-C)") (class "Default")
      (node (ref "LED71") (pin "4") (pinfunction "C_4") (pintype "passive"))
      (node (ref "LED72") (pin "3") (pinfunction "A_3") (pintype "passive"))
    )
    (net (code "197") (name "Net-(LED71C-C)") (class "Default")
      (node (ref "LED71") (pin "5") (pinfunction "C_5") (pintype "passive"))
      (node (ref "LED72") (pin "2") (pinfunction "A_2") (pintype "passive"))
    )
    (net (code "198") (name "Net-(LED73A-A)") (class "Default")
      (node (ref "LED73") (pin "1") (pinfunction "A_1") (pintype "passive"))
      (node (ref "R76") (pin "1") (pinfunction "1_1") (pintype "passive"))
    )
    (net (code "199") (name "Net-(LED73A-C)") (class "Default")
      (node (ref "LED73") (pin "6") (pinfunction "C_6") (pintype "passive"))
      (node (ref "LED74") (pin "1") (pinfunction "A_1") (pintype "passive"))
    )
    (net (code "200") (name "Net-(LED73B-A)") (class "Default")
      (node (ref "LED73") (pin "3") (pinfunction "A_3") (pintype "passive"))
      (node (ref "R75") (pin "1") (pinfunction "1_1") (pintype "passive"))
    )
    (net (code "201") (name "Net-(LED73B-C)") (class "Default")
      (node (ref "LED73") (pin "4") (pinfunction "C_4") (pintype "passive"))
      (node (ref "LED74") (pin "3") (pinfunction "A_3") (pintype "passive"))
    )
    (net (code "202") (name "Net-(LED73C-A)") (class "Default")
      (node (ref "LED73") (pin "2") (pinfunction "A_2") (pintype "passive"))
      (node (ref "R74") (pin "1") (pinfunction "1_1") (pintype "passive"))
    )
    (net (code "203") (name "Net-(LED73C-C)") (class "Default")
      (node (ref "LED73") (pin "5") (pinfunction "C_5") (pintype "passive"))
      (node (ref "LED74") (pin "2") (pinfunction "A_2") (pintype "passive"))
    )
    (net (code "204") (name "Net-(LED74A-C)") (class "Default")
      (node (ref "LED74") (pin "6") (pinfunction "C_6") (pintype "passive"))
      (node (ref "LED75") (pin "1") (pinfunction "A_1") (pintype "passive"))
    )
    (net (code "205") (name "Net-(LED74B-C)") (class "Default")
      (node (ref "LED74") (pin "4") (pinfunction "C_4") (pintype "passive"))
      (node (ref "LED75") (pin "3") (pinfunction "A_3") (pintype "passive"))
    )
    (net (code "206") (name "Net-(LED74C-C)") (class "Default")
      (node (ref "LED74") (pin "5") (pinfunction "C_5") (pintype "passive"))
      (node (ref "LED75") (pin "2") (pinfunction "A_2") (pintype "passive"))
    )
    (net (code "207") (name "Net-(Q1-PadB)") (class "Default")
      (node (ref "Q1") (pin "B") (pinfunction "B_B") (pintype "passive"))
      (node (ref "R45") (pin "2") (pinfunction "2_2") (pintype "passive"))
      (node (ref "R84") (pin "2") (pinfunction "2_2") (pintype "passive"))
    )
    (net (code "208") (name "Net-(Q1-PadC)") (class "Default")
      (node (ref "Q1") (pin "C") (pinfunction "C_C") (pintype "passive"))
      (node (ref "R22") (pin "2") (pinfunction "2_2") (pintype "passive"))
      (node (ref "R25") (pin "2") (pinfunction "2_2") (pintype "passive"))
      (node (ref "R28") (pin "2") (pinfunction "2_2") (pintype "passive"))
      (node (ref "R31") (pin "2") (pinfunction "2_2") (pintype "passive"))
      (node (ref "R34") (pin "2") (pinfunction "2_2") (pintype "passive"))
      (node (ref "R37") (pin "2") (pinfunction "2_2") (pintype "passive"))
      (node (ref "R40") (pin "2") (pinfunction "2_2") (pintype "passive"))
    )
    (net (code "209") (name "Net-(Q2-PadB)") (class "Default")
      (node (ref "Q2") (pin "B") (pinfunction "B_B") (pintype "passive"))
      (node (ref "R44") (pin "2") (pinfunction "2_2") (pintype "passive"))
      (node (ref "R83") (pin "2") (pinfunction "2_2") (pintype "passive"))
    )
    (net (code "210") (name "Net-(Q2-PadC)") (class "Default")
      (node (ref "Q2") (pin "C") (pinfunction "C_C") (pintype "passive"))
      (node (ref "R21") (pin "2") (pinfunction "2_2") (pintype "passive"))
      (node (ref "R24") (pin "2") (pinfunction "2_2") (pintype "passive"))
      (node (ref "R27") (pin "2") (pinfunction "2_2") (pintype "passive"))
      (node (ref "R30") (pin "2") (pinfunction "2_2") (pintype "passive"))
      (node (ref "R33") (pin "2") (pinfunction "2_2") (pintype "passive"))
      (node (ref "R36") (pin "2") (pinfunction "2_2") (pintype "passive"))
      (node (ref "R39") (pin "2") (pinfunction "2_2") (pintype "passive"))
    )
    (net (code "211") (name "Net-(Q3-PadB)") (class "Default")
      (node (ref "Q3") (pin "B") (pinfunction "B_B") (pintype "passive"))
      (node (ref "R43") (pin "2") (pinfunction "2_2") (pintype "passive"))
      (node (ref "R82") (pin "2") (pinfunction "2_2") (pintype "passive"))
    )
    (net (code "212") (name "Net-(Q3-PadC)") (class "Default")
      (node (ref "Q3") (pin "C") (pinfunction "C_C") (pintype "passive"))
      (node (ref "R20") (pin "2") (pinfunction "2_2") (pintype "passive"))
      (node (ref "R23") (pin "2") (pinfunction "2_2") (pintype "passive"))
      (node (ref "R26") (pin "2") (pinfunction "2_2") (pintype "passive"))
      (node (ref "R29") (pin "2") (pinfunction "2_2") (pintype "passive"))
      (node (ref "R32") (pin "2") (pinfunction "2_2") (pintype "passive"))
      (node (ref "R35") (pin "2") (pinfunction "2_2") (pintype "passive"))
      (node (ref "R38") (pin "2") (pinfunction "2_2") (pintype "passive"))
    )
    (net (code "213") (name "Net-(Q5-PadB)") (class "Default")
      (node (ref "Q5") (pin "B") (pinfunction "B_B") (pintype "passive"))
      (node (ref "R51") (pin "2") (pinfunction "2_2") (pintype "passive"))
      (node (ref "R79") (pin "2") (pinfunction "2_2") (pintype "passive"))
    )
    (net (code "214") (name "Net-(Q5-PadC)") (class "Default")
      (node (ref "Q5") (pin "C") (pinfunction "C_C") (pintype "passive"))
      (node (ref "R10") (pin "2") (pinfunction "2_2") (pintype "passive"))
      (node (ref "R13") (pin "2") (pinfunction "2_2") (pintype "passive"))
      (node (ref "R16") (pin "2") (pinfunction "2_2") (pintype "passive"))
      (node (ref "R19") (pin "2") (pinfunction "2_2") (pintype "passive"))
      (node (ref "R4") (pin "2") (pinfunction "2_2") (pintype "passive"))
      (node (ref "R7") (pin "2") (pinfunction "2_2") (pintype "passive"))
    )
    (net (code "215") (name "Net-(Q6-PadB)") (class "Default")
      (node (ref "Q6") (pin "B") (pinfunction "B_B") (pintype "passive"))
      (node (ref "R50") (pin "2") (pinfunction "2_2") (pintype "passive"))
      (node (ref "R80") (pin "2") (pinfunction "2_2") (pintype "passive"))
    )
    (net (code "216") (name "Net-(Q6-PadC)") (class "Default")
      (node (ref "Q6") (pin "C") (pinfunction "C_C") (pintype "passive"))
      (node (ref "R12") (pin "2") (pinfunction "2_2") (pintype "passive"))
      (node (ref "R15") (pin "2") (pinfunction "2_2") (pintype "passive"))
      (node (ref "R18") (pin "2") (pinfunction "2_2") (pintype "passive"))
      (node (ref "R3") (pin "2") (pinfunction "2_2") (pintype "passive"))
      (node (ref "R6") (pin "2") (pinfunction "2_2") (pintype "passive"))
      (node (ref "R9") (pin "2") (pinfunction "2_2") (pintype "passive"))
    )
    (net (code "217") (name "Net-(Q7-PadB)") (class "Default")
      (node (ref "Q7") (pin "B") (pinfunction "B_B") (pintype "passive"))
      (node (ref "R49") (pin "2") (pinfunction "2_2") (pintype "passive"))
      (node (ref "R81") (pin "2") (pinfunction "2_2") (pintype "passive"))
    )
    (net (code "218") (name "Net-(Q7-PadC)") (class "Default")
      (node (ref "Q7") (pin "C") (pinfunction "C_C") (pintype "passive"))
      (node (ref "R11") (pin "2") (pinfunction "2_2") (pintype "passive"))
      (node (ref "R14") (pin "2") (pinfunction "2_2") (pintype "passive"))
      (node (ref "R17") (pin "2") (pinfunction "2_2") (pintype "passive"))
      (node (ref "R2") (pin "2") (pinfunction "2_2") (pintype "passive"))
      (node (ref "R5") (pin "2") (pinfunction "2_2") (pintype "passive"))
      (node (ref "R8") (pin "2") (pinfunction "2_2") (pintype "passive"))
    )
    (net (code "219") (name "Net-(Q8-PadB)") (class "Default")
      (node (ref "Q8") (pin "B") (pinfunction "B_B") (pintype "passive"))
      (node (ref "R57") (pin "2") (pinfunction "2_2") (pintype "passive"))
      (node (ref "R85") (pin "2") (pinfunction "2_2") (pintype "passive"))
    )
    (net (code "220") (name "Net-(Q8-PadC)") (class "Default")
      (node (ref "Q8") (pin "C") (pinfunction "C_C") (pintype "passive"))
      (node (ref "R61") (pin "2") (pinfunction "2_2") (pintype "passive"))
      (node (ref "R64") (pin "2") (pinfunction "2_2") (pintype "passive"))
      (node (ref "R67") (pin "2") (pinfunction "2_2") (pintype "passive"))
      (node (ref "R70") (pin "2") (pinfunction "2_2") (pintype "passive"))
      (node (ref "R73") (pin "2") (pinfunction "2_2") (pintype "passive"))
      (node (ref "R76") (pin "2") (pinfunction "2_2") (pintype "passive"))
    )
    (net (code "221") (name "Net-(Q9-PadB)") (class "Default")
      (node (ref "Q9") (pin "B") (pinfunction "B_B") (pintype "passive"))
      (node (ref "R56") (pin "2") (pinfunction "2_2") (pintype "passive"))
      (node (ref "R86") (pin "2") (pinfunction "2_2") (pintype "passive"))
    )
    (net (code "222") (name "Net-(Q9-PadC)") (class "Default")
      (node (ref "Q9") (pin "C") (pinfunction "C_C") (pintype "passive"))
      (node (ref "R60") (pin "2") (pinfunction "2_2") (pintype "passive"))
      (node (ref "R63") (pin "2") (pinfunction "2_2") (pintype "passive"))
      (node (ref "R66") (pin "2") (pinfunction "2_2") (pintype "passive"))
      (node (ref "R69") (pin "2") (pinfunction "2_2") (pintype "passive"))
      (node (ref "R72") (pin "2") (pinfunction "2_2") (pintype "passive"))
      (node (ref "R75") (pin "2") (pinfunction "2_2") (pintype "passive"))
    )
    (net (code "223") (name "Net-(Q10-PadB)") (class "Default")
      (node (ref "Q10") (pin "B") (pinfunction "B_B") (pintype "passive"))
      (node (ref "R55") (pin "2") (pinfunction "2_2") (pintype "passive"))
      (node (ref "R87") (pin "2") (pinfunction "2_2") (pintype "passive"))
    )
    (net (code "224") (name "Net-(Q10-PadC)") (class "Default")
      (node (ref "Q10") (pin "C") (pinfunction "C_C") (pintype "passive"))
      (node (ref "R59") (pin "2") (pinfunction "2_2") (pintype "passive"))
      (node (ref "R62") (pin "2") (pinfunction "2_2") (pintype "passive"))
      (node (ref "R65") (pin "2") (pinfunction "2_2") (pintype "passive"))
      (node (ref "R68") (pin "2") (pinfunction "2_2") (pintype "passive"))
      (node (ref "R71") (pin "2") (pinfunction "2_2") (pintype "passive"))
      (node (ref "R74") (pin "2") (pinfunction "2_2") (pintype "passive"))
    )
    (net (code "225") (name "Net-(S1-S)") (class "Default")
      (node (ref "R42") (pin "2") (pinfunction "2_2") (pintype "passive"))
      (node (ref "S1") (pin "1") (pinfunction "S_1") (pintype "passive"))
      (node (ref "S1") (pin "2") (pinfunction "S1_2") (pintype "passive"))
      (node (ref "U1") (pin "16") (pinfunction "PB2_16") (pintype "bidirectional"))
    )
    (net (code "226") (name "Net-(T1-B)") (class "Default")
      (node (ref "R47") (pin "2") (pinfunction "2_2") (pintype "passive"))
      (node (ref "T1") (pin "2") (pinfunction "B_2") (pintype "passive"))
    )
    (net (code "227") (name "Net-(T1-C)") (class "Default")
      (node (ref "R82") (pin "1") (pinfunction "1_1") (pintype "passive"))
      (node (ref "T1") (pin "3") (pinfunction "C_3") (pintype "passive"))
    )
    (net (code "228") (name "Net-(T2-B)") (class "Default")
      (node (ref "R46") (pin "2") (pinfunction "2_2") (pintype "passive"))
      (node (ref "T2") (pin "2") (pinfunction "B_2") (pintype "passive"))
    )
    (net (code "229") (name "Net-(T2-C)") (class "Default")
      (node (ref "R83") (pin "1") (pinfunction "1_1") (pintype "passive"))
      (node (ref "T2") (pin "3") (pinfunction "C_3") (pintype "passive"))
    )
    (net (code "230") (name "Net-(T3-B)") (class "Default")
      (node (ref "R48") (pin "2") (pinfunction "2_2") (pintype "passive"))
      (node (ref "T3") (pin "2") (pinfunction "B_2") (pintype "passive"))
    )
    (net (code "231") (name "Net-(T3-C)") (class "Default")
      (node (ref "R84") (pin "1") (pinfunction "1_1") (pintype "passive"))
      (node (ref "T3") (pin "3") (pinfunction "C_3") (pintype "passive"))
    )
    (net (code "232") (name "Net-(T4-B)") (class "Default")
      (node (ref "R53") (pin "2") (pinfunction "2_2") (pintype "passive"))
      (node (ref "T4") (pin "2") (pinfunction "B_2") (pintype "passive"))
    )
    (net (code "233") (name "Net-(T4-C)") (class "Default")
      (node (ref "R81") (pin "1") (pinfunction "1_1") (pintype "passive"))
      (node (ref "T4") (pin "3") (pinfunction "C_3") (pintype "passive"))
    )
    (net (code "234") (name "Net-(T5-B)") (class "Default")
      (node (ref "R52") (pin "2") (pinfunction "2_2") (pintype "passive"))
      (node (ref "T5") (pin "2") (pinfunction "B_2") (pintype "passive"))
    )
    (net (code "235") (name "Net-(T5-C)") (class "Default")
      (node (ref "R80") (pin "1") (pinfunction "1_1") (pintype "passive"))
      (node (ref "T5") (pin "3") (pinfunction "C_3") (pintype "passive"))
    )
    (net (code "236") (name "Net-(T6-B)") (class "Default")
      (node (ref "R54") (pin "2") (pinfunction "2_2") (pintype "passive"))
      (node (ref "T6") (pin "2") (pinfunction "B_2") (pintype "passive"))
    )
    (net (code "237") (name "Net-(T6-C)") (class "Default")
      (node (ref "R79") (pin "1") (pinfunction "1_1") (pintype "passive"))
      (node (ref "T6") (pin "3") (pinfunction "C_3") (pintype "passive"))
    )
    (net (code "238") (name "Net-(T7-B)") (class "Default")
      (node (ref "R77") (pin "2") (pinfunction "2_2") (pintype "passive"))
      (node (ref "T7") (pin "2") (pinfunction "B_2") (pintype "passive"))
    )
    (net (code "239") (name "Net-(T7-C)") (class "Default")
      (node (ref "R87") (pin "1") (pinfunction "1_1") (pintype "passive"))
      (node (ref "T7") (pin "3") (pinfunction "C_3") (pintype "passive"))
    )
    (net (code "240") (name "Net-(T8-B)") (class "Default")
      (node (ref "R58") (pin "2") (pinfunction "2_2") (pintype "passive"))
      (node (ref "T8") (pin "2") (pinfunction "B_2") (pintype "passive"))
    )
    (net (code "241") (name "Net-(T8-C)") (class "Default")
      (node (ref "R86") (pin "1") (pinfunction "1_1") (pintype "passive"))
      (node (ref "T8") (pin "3") (pinfunction "C_3") (pintype "passive"))
    )
    (net (code "242") (name "Net-(T9-B)") (class "Default")
      (node (ref "R78") (pin "2") (pinfunction "2_2") (pintype "passive"))
      (node (ref "T9") (pin "2") (pinfunction "B_2") (pintype "passive"))
    )
    (net (code "243") (name "Net-(T9-C)") (class "Default")
      (node (ref "R85") (pin "1") (pinfunction "1_1") (pintype "passive"))
      (node (ref "T9") (pin "3") (pinfunction "C_3") (pintype "passive"))
    )
    (net (code "244") (name "VCC") (class "Default")
      (node (ref "IC3") (pin "7") (pinfunction "VBACK_7") (pintype "input"))
      (node (ref "IC3") (pin "8") (pinfunction "VCC_8") (pintype "power_in"))
      (node (ref "R1") (pin "2") (pinfunction "2_2") (pintype "passive"))
      (node (ref "R41") (pin "1") (pinfunction "1_1") (pintype "passive"))
      (node (ref "R42") (pin "1") (pinfunction "1_1") (pintype "passive"))
      (node (ref "U1") (pin "20") (pinfunction "AVCC_20") (pintype "power_in"))
      (node (ref "U1") (pin "21") (pinfunction "AREF_21") (pintype "input"))
      (node (ref "U1") (pin "7") (pinfunction "VCC_7") (pintype "power_in"))
    )
    (net (code "245") (name "unconnected-(IC1A-QH*-Pad9)") (class "Default")
      (node (ref "IC1") (pin "9") (pinfunction "QH*_9") (pintype "tri_state"))
    )
    (net (code "246") (name "unconnected-(U1-GND-Pad22)") (class "Default")
      (node (ref "U1") (pin "22") (pinfunction "GND_22") (pintype "passive"))
    )
    (net (code "247") (name "unconnected-(U1-GND_2-Pad8)") (class "Default")
      (node (ref "U1") (pin "8") (pinfunction "GND_2_8") (pintype "passive"))
    )
    (net (code "248") (name "unconnected-(U1-PB0-Pad14)") (class "Default")
      (node (ref "U1") (pin "14") (pinfunction "PB0_14") (pintype "bidirectional"))
    )
    (net (code "249") (name "unconnected-(U1-PB1-Pad15)") (class "Default")
      (node (ref "U1") (pin "15") (pinfunction "PB1_15") (pintype "bidirectional"))
    )
    (net (code "250") (name "unconnected-(U1-PB6-Pad9)") (class "Default")
      (node (ref "U1") (pin "9") (pinfunction "PB6_9") (pintype "bidirectional"))
    )
    (net (code "251") (name "unconnected-(U1-PB7-Pad10)") (class "Default")
      (node (ref "U1") (pin "10") (pinfunction "PB7_10") (pintype "bidirectional"))
    )
    (net (code "252") (name "unconnected-(U1-PC0-Pad23)") (class "Default")
      (node (ref "U1") (pin "23") (pinfunction "PC0_23") (pintype "bidirectional"))
    )
    (net (code "253") (name "unconnected-(U1-PC1-Pad24)") (class "Default")
      (node (ref "U1") (pin "24") (pinfunction "PC1_24") (pintype "bidirectional"))
    )
    (net (code "254") (name "unconnected-(U1-PC2-Pad25)") (class "Default")
      (node (ref "U1") (pin "25") (pinfunction "PC2_25") (pintype "bidirectional"))
    )
    (net (code "255") (name "unconnected-(U1-PC3-Pad26)") (class "Default")
      (node (ref "U1") (pin "26") (pinfunction "PC3_26") (pintype "bidirectional"))
    )
    (net (code "256") (name "unconnected-(U1-PC6-Pad1)") (class "Default")
      (node (ref "U1") (pin "1") (pinfunction "PC6_1") (pintype "bidirectional"))
    )
    (net (code "257") (name "unconnected-(U1-PD0-Pad2)") (class "Default")
      (node (ref "U1") (pin "2") (pinfunction "PD0_2") (pintype "bidirectional"))
    )
    (net (code "258") (name "unconnected-(U1-PD1-Pad3)") (class "Default")
      (node (ref "U1") (pin "3") (pinfunction "PD1_3") (pintype "bidirectional"))
    )
    (net (code "259") (name "unconnected-(U1-PD2-Pad4)") (class "Default")
      (node (ref "U1") (pin "4") (pinfunction "PD2_4") (pintype "bidirectional"))
    )
    (net (code "260") (name "unconnected-(U1-PD3-Pad5)") (class "Default")
      (node (ref "U1") (pin "5") (pinfunction "PD3_5") (pintype "bidirectional"))
    )
    (net (code "261") (name "unconnected-(U1-PD4-Pad6)") (class "Default")
      (node (ref "U1") (pin "6") (pinfunction "PD4_6") (pintype "bidirectional"))
    )
    (net (code "262") (name "unconnected-(U1-PD5-Pad11)") (class "Default")
      (node (ref "U1") (pin "11") (pinfunction "PD5_11") (pintype "bidirectional"))
    )
    (net (code "263") (name "unconnected-(U1-PD6-Pad12)") (class "Default")
      (node (ref "U1") (pin "12") (pinfunction "PD6_12") (pintype "bidirectional"))
    )
    (net (code "264") (name "unconnected-(U1-PD7-Pad13)") (class "Default")
      (node (ref "U1") (pin "13") (pinfunction "PD7_13") (pintype "bidirectional"))
    )
    (net (code "265") (name "unconnected-(U2-COM-Pad9)") (class "Default")
      (node (ref "U2") (pin "9") (pinfunction "COM_9") (pintype "output"))
    )
  )
)
